# ball_dropper_rev3.net
KiCad netlist of a schematic drawn in Altium Designer
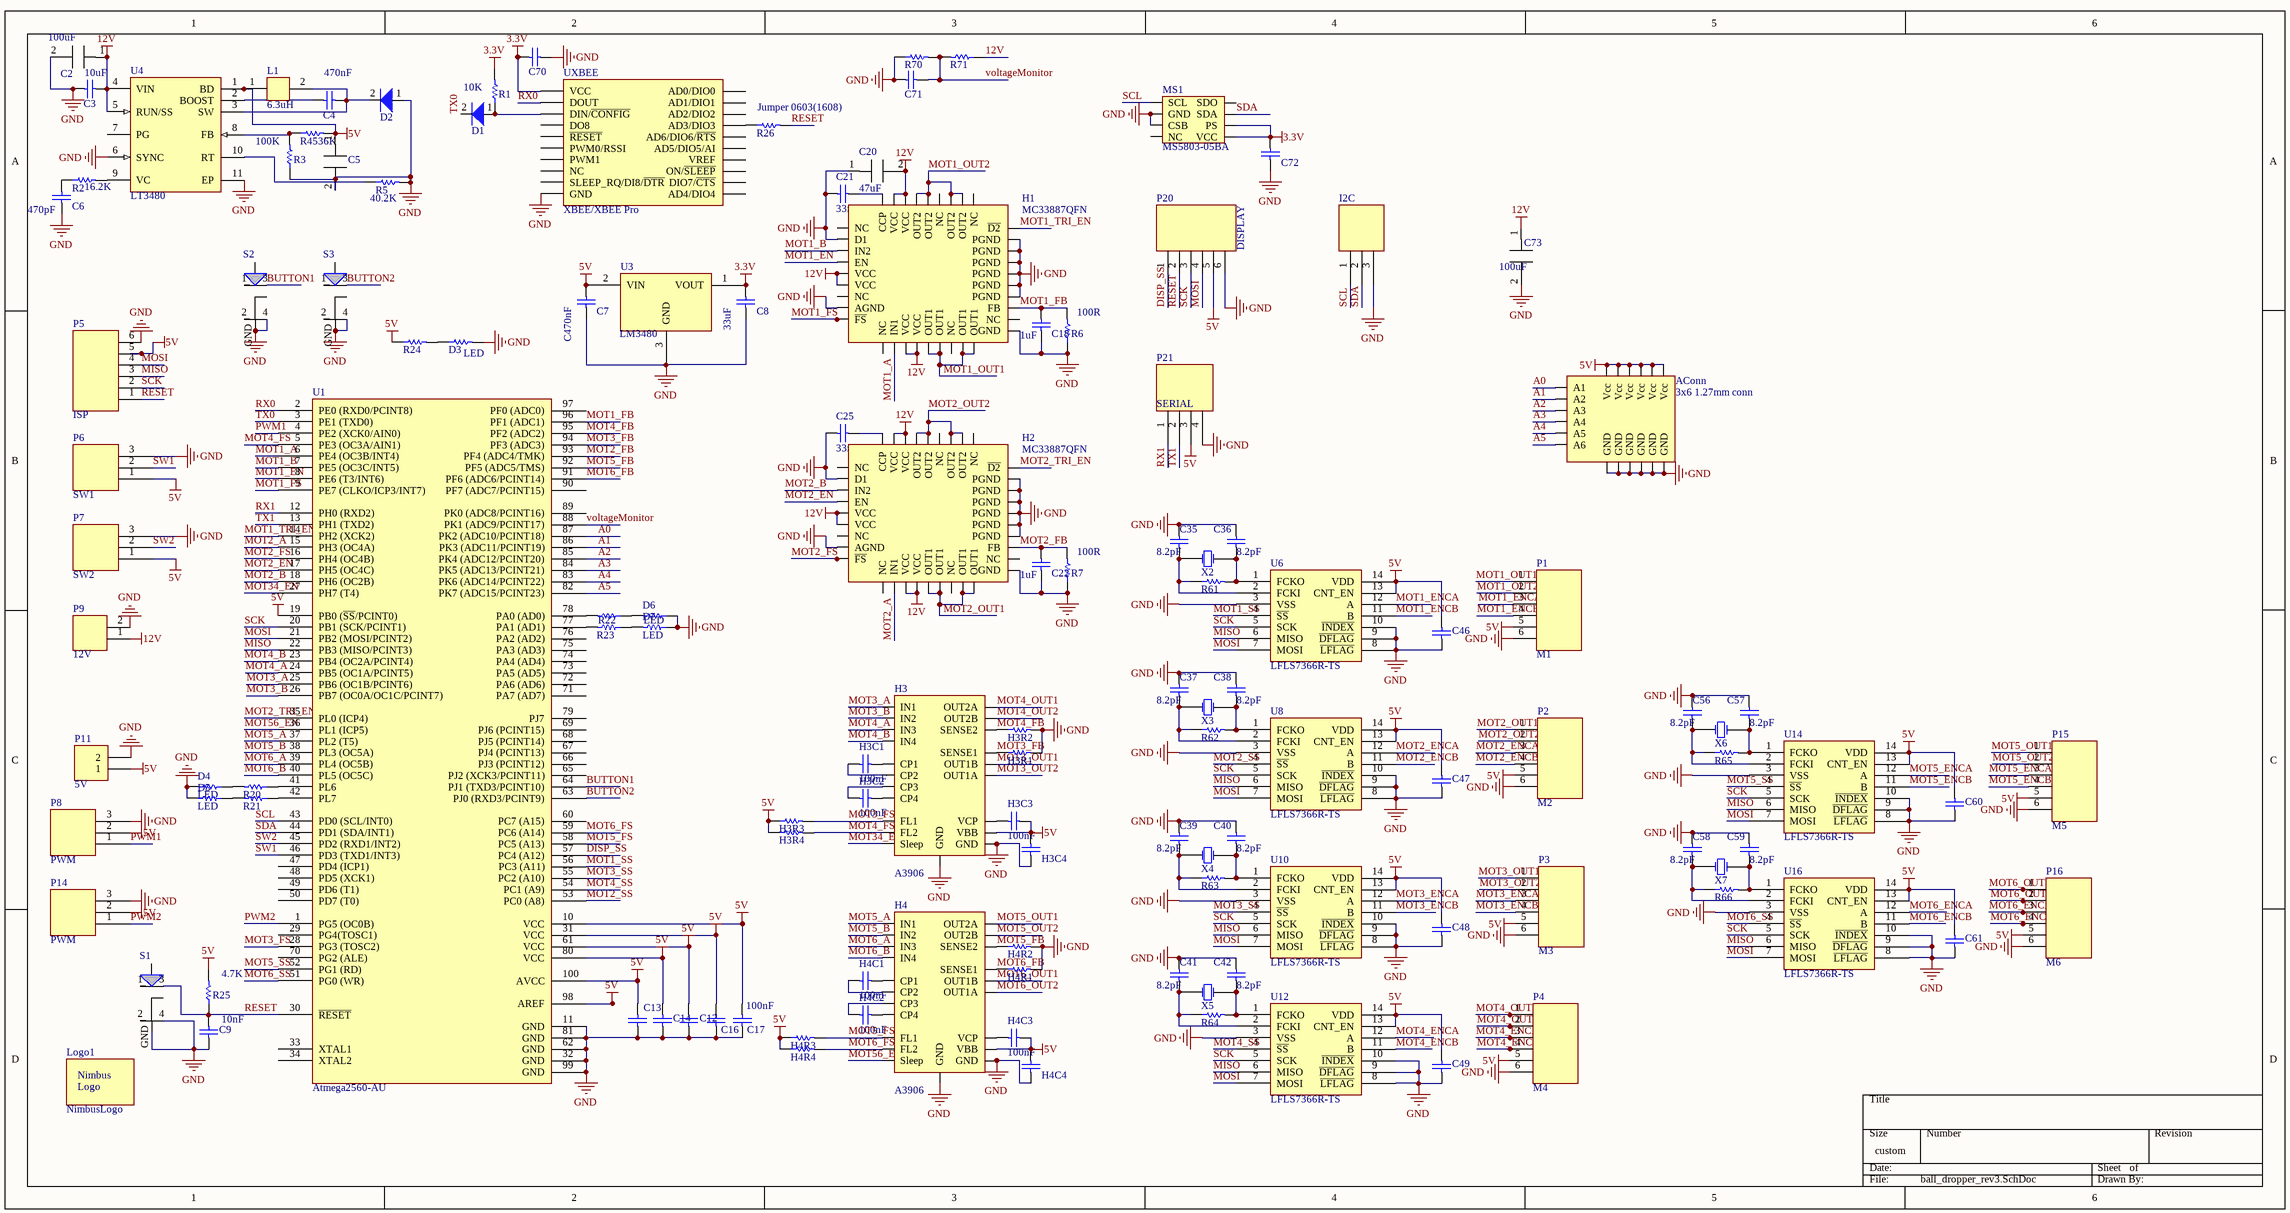
[diagram p0: ball_dropper_rev3.SchDoc]

(export (version "E")
  (design (tool "Eeschema 10.0.6"))
  (components
    (comp (ref "AConn")
      (value "3x6 1.27mm conn")
      (footprint "3x6 1.27mm conn")
      (libsource (lib "Integrated_Library") (part "3x6 1.27mm conn"))
    )
    (comp (ref "C2")
      (value "100uF")
      (footprint "TantalumCap7343")
      (libsource (lib "Integrated_Library") (part "TantalumCap7343"))
    )
    (comp (ref "C3")
      (value "10uF")
      (footprint "CAPC0603(1608)100_M")
      (description "CAP 10uF 10V ±20% 0603 (1608 Metric) Thickness 1mm SMD")
      (fields (field (name "TOLERANCE") "±20%"))
      (libsource (lib "Altium Content Vault") (part "CMP-1035-02800-1"))
    )
    (comp (ref "C4")
      (value "470nF")
      (footprint "CAPC0603(1608)100_N")
      (description "CAP 470nF 16V ±20% 0603 (1608 Metric) Thickness 1mm SMD")
      (fields (field (name "TOLERANCE") "±20%"))
      (libsource (lib "Altium Content Vault") (part "CMP-1035-02701-1"))
    )
    (comp (ref "C5")
      (value "47uF")
      (footprint "TantalumCap7343")
      (libsource (lib "Integrated_Library") (part "TantalumCap7343"))
    )
    (comp (ref "C6")
      (value "470pF")
      (footprint "CAPC0603(1608)100_N")
      (description "CAP 470pF 16V ±2% 0603 (1608 Metric) Thickness 1mm SMD")
      (fields (field (name "TOLERANCE") "±2%"))
      (libsource (lib "Altium Content Vault") (part "CMP-1035-01664-1"))
    )
    (comp (ref "C7")
      (value "C470nF")
      (footprint "CAPC0603(1608)100_N")
      (description "CAP 470nF 10V ±10% 0603 (1608 Metric) Thickness 1mm SMD")
      (fields (field (name "TOLERANCE") "±10%"))
      (libsource (lib "Altium Content Vault") (part "CMP-1035-02696-1"))
    )
    (comp (ref "C8")
      (value "33uF")
      (footprint "CAPC1206(3216)190_M")
      (description "CAP 33uF 10V ±20% 1206 (3216 Metric) Thickness 1.9mm SMD")
      (fields (field (name "TOLERANCE") "±20%"))
      (libsource (lib "Altium Content Vault") (part "CMP-1037-04997-1"))
    )
    (comp (ref "C9")
      (value "10nF")
      (footprint "CAPC0603(1608)100_M")
      (description "CAP 10nF 10V ±2% 0603 (1608 Metric) Thickness 1mm SMD")
      (fields (field (name "TOLERANCE") "±2%"))
      (libsource (lib "Altium Content Vault") (part "CMP-1035-02304-1"))
    )
    (comp (ref "C12")
      (value "100nF")
      (footprint "CAPC0603(1608)100_N")
      (description "CAP 100nF 10V -20% to +80% 0603 (1608 Metric) Thickness 1mm SMD")
      (fields (field (name "TOLERANCE") "-20% to +80%"))
      (libsource (lib "Altium Content Vault") (part "CMP-1035-02582-1"))
    )
    (comp (ref "C13")
      (value "100nF")
      (footprint "CAPC0603(1608)100_N")
      (description "CAP 100nF 10V -20% to +80% 0603 (1608 Metric) Thickness 1mm SMD")
      (fields (field (name "TOLERANCE") "-20% to +80%"))
      (libsource (lib "Altium Content Vault") (part "CMP-1035-02582-1"))
    )
    (comp (ref "C14")
      (value "100nF")
      (footprint "CAPC0603(1608)100_N")
      (description "CAP 100nF 10V -20% to +80% 0603 (1608 Metric) Thickness 1mm SMD")
      (fields (field (name "TOLERANCE") "-20% to +80%"))
      (libsource (lib "Altium Content Vault") (part "CMP-1035-02582-1"))
    )
    (comp (ref "C16")
      (value "100nF")
      (footprint "CAPC0603(1608)100_N")
      (description "CAP 100nF 10V -20% to +80% 0603 (1608 Metric) Thickness 1mm SMD")
      (fields (field (name "TOLERANCE") "-20% to +80%"))
      (libsource (lib "Altium Content Vault") (part "CMP-1035-02582-1"))
    )
    (comp (ref "C17")
      (value "100nF")
      (footprint "CAPC0603(1608)100_N")
      (description "CAP 100nF 10V -20% to +80% 0603 (1608 Metric) Thickness 1mm SMD")
      (fields (field (name "TOLERANCE") "-20% to +80%"))
      (libsource (lib "Altium Content Vault") (part "CMP-1035-02582-1"))
    )
    (comp (ref "C18")
      (value "1uF")
      (footprint "CAPC0603(1608)100_N")
      (description "CAP 1uF 25V ±10% 0603 (1608 Metric) Thickness 1mm SMD")
      (fields (field (name "TOLERANCE") "±10%"))
      (libsource (lib "Altium Content Vault") (part "CMP-1035-02740-1"))
    )
    (comp (ref "C20")
      (value "47uF")
      (footprint "TantalumCap7343")
      (libsource (lib "Integrated_Library") (part "TantalumCap7343"))
    )
    (comp (ref "C21")
      (value "33nF")
      (footprint "CAPC0603(1608)100_N")
      (description "CAP 33nF 25V ±5% 0603 (1608 Metric) Thickness 1mm SMD")
      (fields (field (name "TOLERANCE") "±5%"))
      (libsource (lib "Altium Content Vault") (part "CMP-1035-02463-1"))
    )
    (comp (ref "C22")
      (value "1uF")
      (footprint "CAPC0603(1608)100_N")
      (description "CAP 1uF 25V ±10% 0603 (1608 Metric) Thickness 1mm SMD")
      (fields (field (name "TOLERANCE") "±10%"))
      (libsource (lib "Altium Content Vault") (part "CMP-1035-02740-1"))
    )
    (comp (ref "C25")
      (value "33nF")
      (footprint "CAPC0603(1608)100_N")
      (description "CAP 33nF 25V ±5% 0603 (1608 Metric) Thickness 1mm SMD")
      (fields (field (name "TOLERANCE") "±5%"))
      (libsource (lib "Altium Content Vault") (part "CMP-1035-02463-1"))
    )
    (comp (ref "C35")
      (value "8.2pF")
      (footprint "CAPC0603(1608)100_N")
      (description "CAP 8.2pF 10V ±0.1pF 0603 (1608 Metric) Thickness 1mm SMD")
      (fields (field (name "TOLERANCE") "±0.1pF"))
      (libsource (lib "Altium Content Vault") (part "CMP-1035-00477-1"))
    )
    (comp (ref "C36")
      (value "8.2pF")
      (footprint "CAPC0603(1608)100_N")
      (description "CAP 8.2pF 10V ±0.1pF 0603 (1608 Metric) Thickness 1mm SMD")
      (fields (field (name "TOLERANCE") "±0.1pF"))
      (libsource (lib "Altium Content Vault") (part "CMP-1035-00477-1"))
    )
    (comp (ref "C37")
      (value "8.2pF")
      (footprint "CAPC0603(1608)100_N")
      (description "CAP 8.2pF 10V ±0.1pF 0603 (1608 Metric) Thickness 1mm SMD")
      (fields (field (name "TOLERANCE") "±0.1pF"))
      (libsource (lib "Altium Content Vault") (part "CMP-1035-00477-1"))
    )
    (comp (ref "C38")
      (value "8.2pF")
      (footprint "CAPC0603(1608)100_N")
      (description "CAP 8.2pF 10V ±0.1pF 0603 (1608 Metric) Thickness 1mm SMD")
      (fields (field (name "TOLERANCE") "±0.1pF"))
      (libsource (lib "Altium Content Vault") (part "CMP-1035-00477-1"))
    )
    (comp (ref "C39")
      (value "8.2pF")
      (footprint "CAPC0603(1608)100_N")
      (description "CAP 8.2pF 10V ±0.1pF 0603 (1608 Metric) Thickness 1mm SMD")
      (fields (field (name "TOLERANCE") "±0.1pF"))
      (libsource (lib "Altium Content Vault") (part "CMP-1035-00477-1"))
    )
    (comp (ref "C40")
      (value "8.2pF")
      (footprint "CAPC0603(1608)100_N")
      (description "CAP 8.2pF 10V ±0.1pF 0603 (1608 Metric) Thickness 1mm SMD")
      (fields (field (name "TOLERANCE") "±0.1pF"))
      (libsource (lib "Altium Content Vault") (part "CMP-1035-00477-1"))
    )
    (comp (ref "C41")
      (value "8.2pF")
      (footprint "CAPC0603(1608)100_N")
      (description "CAP 8.2pF 10V ±0.1pF 0603 (1608 Metric) Thickness 1mm SMD")
      (fields (field (name "TOLERANCE") "±0.1pF"))
      (libsource (lib "Altium Content Vault") (part "CMP-1035-00477-1"))
    )
    (comp (ref "C42")
      (value "8.2pF")
      (footprint "CAPC0603(1608)100_N")
      (description "CAP 8.2pF 10V ±0.1pF 0603 (1608 Metric) Thickness 1mm SMD")
      (fields (field (name "TOLERANCE") "±0.1pF"))
      (libsource (lib "Altium Content Vault") (part "CMP-1035-00477-1"))
    )
    (comp (ref "C46")
      (value "100nF")
      (footprint "CAPC0603(1608)100_N")
      (description "CAP 100nF 10V -20% to +80% 0603 (1608 Metric) Thickness 1mm SMD")
      (fields (field (name "TOLERANCE") "-20% to +80%"))
      (libsource (lib "Altium Content Vault") (part "CMP-1035-02582-1"))
    )
    (comp (ref "C47")
      (value "100nF")
      (footprint "CAPC0603(1608)100_N")
      (description "CAP 100nF 10V -20% to +80% 0603 (1608 Metric) Thickness 1mm SMD")
      (fields (field (name "TOLERANCE") "-20% to +80%"))
      (libsource (lib "Altium Content Vault") (part "CMP-1035-02582-1"))
    )
    (comp (ref "C48")
      (value "100nF")
      (footprint "CAPC0603(1608)100_N")
      (description "CAP 100nF 10V -20% to +80% 0603 (1608 Metric) Thickness 1mm SMD")
      (fields (field (name "TOLERANCE") "-20% to +80%"))
      (libsource (lib "Altium Content Vault") (part "CMP-1035-02582-1"))
    )
    (comp (ref "C49")
      (value "100nF")
      (footprint "CAPC0603(1608)100_N")
      (description "CAP 100nF 10V -20% to +80% 0603 (1608 Metric) Thickness 1mm SMD")
      (fields (field (name "TOLERANCE") "-20% to +80%"))
      (libsource (lib "Altium Content Vault") (part "CMP-1035-02582-1"))
    )
    (comp (ref "C56")
      (value "8.2pF")
      (footprint "CAPC0603(1608)100_N")
      (description "CAP 8.2pF 10V ±0.1pF 0603 (1608 Metric) Thickness 1mm SMD")
      (fields (field (name "TOLERANCE") "±0.1pF"))
      (libsource (lib "Altium Content Vault") (part "CMP-1035-00477-1"))
    )
    (comp (ref "C57")
      (value "8.2pF")
      (footprint "CAPC0603(1608)100_N")
      (description "CAP 8.2pF 10V ±0.1pF 0603 (1608 Metric) Thickness 1mm SMD")
      (fields (field (name "TOLERANCE") "±0.1pF"))
      (libsource (lib "Altium Content Vault") (part "CMP-1035-00477-1"))
    )
    (comp (ref "C58")
      (value "8.2pF")
      (footprint "CAPC0603(1608)100_N")
      (description "CAP 8.2pF 10V ±0.1pF 0603 (1608 Metric) Thickness 1mm SMD")
      (fields (field (name "TOLERANCE") "±0.1pF"))
      (libsource (lib "Altium Content Vault") (part "CMP-1035-00477-1"))
    )
    (comp (ref "C59")
      (value "8.2pF")
      (footprint "CAPC0603(1608)100_N")
      (description "CAP 8.2pF 10V ±0.1pF 0603 (1608 Metric) Thickness 1mm SMD")
      (fields (field (name "TOLERANCE") "±0.1pF"))
      (libsource (lib "Altium Content Vault") (part "CMP-1035-00477-1"))
    )
    (comp (ref "C60")
      (value "100nF")
      (footprint "CAPC0603(1608)100_N")
      (description "CAP 100nF 10V -20% to +80% 0603 (1608 Metric) Thickness 1mm SMD")
      (fields (field (name "TOLERANCE") "-20% to +80%"))
      (libsource (lib "Altium Content Vault") (part "CMP-1035-02582-1"))
    )
    (comp (ref "C61")
      (value "100nF")
      (footprint "CAPC0603(1608)100_N")
      (description "CAP 100nF 10V -20% to +80% 0603 (1608 Metric) Thickness 1mm SMD")
      (fields (field (name "TOLERANCE") "-20% to +80%"))
      (libsource (lib "Altium Content Vault") (part "CMP-1035-02582-1"))
    )
    (comp (ref "C70")
      (value "CAP 10uF 10V 1206(3216)")
      (footprint "CAPC1206(3216)190_N")
      (description "CAP 10uF 10V Â±5% 1206 (3216 Metric) Thickness 1.9mm SMD")
      (fields (field (name "TOLERANCE") "Â±5%"))
      (libsource (lib "Altium Content Vault") (part "CMP-1037-04966-1"))
    )
    (comp (ref "C71")
      (value "CAP 100nF 25V 0603(1608)")
      (footprint "CAPC0603(1608)100_N")
      (description "CAP 100nF 25V ±5% 0603 (1608 Metric) Thickness 1mm SMD")
      (fields (field (name "TOLERANCE") "Â±5%"))
      (libsource (lib "Altium Content Vault") (part "CMP-1035-02587-1"))
    )
    (comp (ref "C72")
      (value "CAP 100nF 25V 0603(1608)")
      (footprint "CAPC0603(1608)100_N")
      (description "CAP 100nF 25V ±5% 0603 (1608 Metric) Thickness 1mm SMD")
      (fields (field (name "TOLERANCE") "Â±5%"))
      (libsource (lib "Altium Content Vault") (part "CMP-1035-02587-1"))
    )
    (comp (ref "C73")
      (value "100uF")
      (footprint "TantalumCap7343")
      (libsource (lib "Integrated_Library") (part "TantalumCap7343"))
    )
    (comp (ref "D1")
      (value "diode_MBRA210LT3G")
      (footprint "C1206")
      (libsource (lib "Integrated_Library") (part "diode_MBRA210LT3G"))
    )
    (comp (ref "D2")
      (value "diode_B340A")
      (footprint "diode_B340A")
      (libsource (lib "Integrated_Library") (part "diode_B340A"))
    )
    (comp (ref "D3")
      (value "LED")
      (footprint "RESC0603(1608)_N")
      (fields (field (name "POWER") "None"))
      (libsource (lib "Altium Content Vault") (part "CMP-1012-00001-1"))
    )
    (comp (ref "D4")
      (value "LED")
      (footprint "RESC0603(1608)_N")
      (fields (field (name "POWER") "None"))
      (libsource (lib "Altium Content Vault") (part "CMP-1012-00001-1"))
    )
    (comp (ref "D5")
      (value "LED")
      (footprint "RESC0603(1608)_N")
      (fields (field (name "POWER") "None"))
      (libsource (lib "Altium Content Vault") (part "CMP-1012-00001-1"))
    )
    (comp (ref "D6")
      (value "LED")
      (footprint "RESC0603(1608)_N")
      (fields (field (name "POWER") "None"))
      (libsource (lib "Altium Content Vault") (part "CMP-1012-00001-1"))
    )
    (comp (ref "D7")
      (value "LED")
      (footprint "RESC0603(1608)_N")
      (fields (field (name "POWER") "None"))
      (libsource (lib "Altium Content Vault") (part "CMP-1012-00001-1"))
    )
    (comp (ref "H1")
      (value "MC33887QFN")
      (footprint "MC33887-QFN")
      (libsource (lib "Integrated_Library") (part "MC33887QFN"))
    )
    (comp (ref "H2")
      (value "MC33887QFN")
      (footprint "MC33887-QFN")
      (libsource (lib "Integrated_Library") (part "MC33887QFN"))
    )
    (comp (ref "H3")
      (value "A3906")
      (footprint "A3906-QFN")
      (libsource (lib "Integrated_Library") (part "A3906"))
    )
    (comp (ref "H3C1")
      (value "100nF")
      (footprint "CAPC0603(1608)100_N")
      (description "CAP 100nF 10V -20% to +80% 0603 (1608 Metric) Thickness 1mm SMD")
      (fields (field (name "TOLERANCE") "-20% to +80%"))
      (libsource (lib "Altium Content Vault") (part "CMP-1035-02582-1"))
    )
    (comp (ref "H3C2")
      (value "100nF")
      (footprint "CAPC0603(1608)100_N")
      (description "CAP 100nF 10V -20% to +80% 0603 (1608 Metric) Thickness 1mm SMD")
      (fields (field (name "TOLERANCE") "-20% to +80%"))
      (libsource (lib "Altium Content Vault") (part "CMP-1035-02582-1"))
    )
    (comp (ref "H3C3")
      (value "100nF")
      (footprint "CAPC0603(1608)100_N")
      (description "CAP 100nF 10V -20% to +80% 0603 (1608 Metric) Thickness 1mm SMD")
      (fields (field (name "TOLERANCE") "-20% to +80%"))
      (libsource (lib "Altium Content Vault") (part "CMP-1035-02582-1"))
    )
    (comp (ref "H3C4")
      (value "CAP 10uF 10V 0603(1608)")
      (footprint "CAPC0603(1608)100_N")
      (description "CAP 10uF 10V Â±10% 0603 (1608 Metric) Thickness 1mm SMD")
      (fields (field (name "TOLERANCE") "Â±10%"))
      (libsource (lib "Altium Content Vault") (part "CMP-1035-02799-1"))
    )
    (comp (ref "H3R1")
      (value "0.2R 5% 1206(3216)")
      (footprint "RESC1206(3216)_N")
      (description "0.2R 0.25W 5% 1206 (3216 Metric)  SMD")
      (fields (field (name "TOLERANCE") "5 %") (field (name "POWER") "0.25 W"))
      (libsource (lib "Altium Content Vault") (part "CMP-1014-00002-1"))
    )
    (comp (ref "H3R2")
      (value "0.2R 5% 1206(3216)")
      (footprint "RESC1206(3216)_N")
      (description "0.2R 0.25W 5% 1206 (3216 Metric)  SMD")
      (fields (field (name "TOLERANCE") "5 %") (field (name "POWER") "0.25 W"))
      (libsource (lib "Altium Content Vault") (part "CMP-1014-00002-1"))
    )
    (comp (ref "H3R3")
      (value "1M 5% 0603(1608)")
      (footprint "RESC0603(1608)_N")
      (description "1M 0.1W 5% 0603 (1608 Metric)  SMD")
      (fields (field (name "POWER") "0.1 W") (field (name "TOLERANCE") "5 %"))
      (libsource (lib "Altium Content Vault") (part "CMP-1012-00054-1"))
    )
    (comp (ref "H3R4")
      (value "1M 5% 0603(1608)")
      (footprint "RESC0603(1608)_N")
      (description "1M 0.1W 5% 0603 (1608 Metric)  SMD")
      (fields (field (name "POWER") "0.1 W") (field (name "TOLERANCE") "5 %"))
      (libsource (lib "Altium Content Vault") (part "CMP-1012-00054-1"))
    )
    (comp (ref "H4")
      (value "A3906")
      (footprint "A3906-QFN")
      (libsource (lib "Integrated_Library") (part "A3906"))
    )
    (comp (ref "H4C1")
      (value "100nF")
      (footprint "CAPC0603(1608)100_N")
      (description "CAP 100nF 10V -20% to +80% 0603 (1608 Metric) Thickness 1mm SMD")
      (fields (field (name "TOLERANCE") "-20% to +80%"))
      (libsource (lib "Altium Content Vault") (part "CMP-1035-02582-1"))
    )
    (comp (ref "H4C2")
      (value "100nF")
      (footprint "CAPC0603(1608)100_N")
      (description "CAP 100nF 10V -20% to +80% 0603 (1608 Metric) Thickness 1mm SMD")
      (fields (field (name "TOLERANCE") "-20% to +80%"))
      (libsource (lib "Altium Content Vault") (part "CMP-1035-02582-1"))
    )
    (comp (ref "H4C3")
      (value "100nF")
      (footprint "CAPC0603(1608)100_N")
      (description "CAP 100nF 10V -20% to +80% 0603 (1608 Metric) Thickness 1mm SMD")
      (fields (field (name "TOLERANCE") "-20% to +80%"))
      (libsource (lib "Altium Content Vault") (part "CMP-1035-02582-1"))
    )
    (comp (ref "H4C4")
      (value "CAP 10uF 10V 0603(1608)")
      (footprint "CAPC0603(1608)100_N")
      (description "CAP 10uF 10V Â±10% 0603 (1608 Metric) Thickness 1mm SMD")
      (fields (field (name "TOLERANCE") "Â±10%"))
      (libsource (lib "Altium Content Vault") (part "CMP-1035-02799-1"))
    )
    (comp (ref "H4R1")
      (value "0.2R 5% 1206(3216)")
      (footprint "RESC1206(3216)_N")
      (description "0.2R 0.25W 5% 1206 (3216 Metric)  SMD")
      (fields (field (name "TOLERANCE") "5 %") (field (name "POWER") "0.25 W"))
      (libsource (lib "Altium Content Vault") (part "CMP-1014-00002-1"))
    )
    (comp (ref "H4R2")
      (value "0.2R 5% 1206(3216)")
      (footprint "RESC1206(3216)_N")
      (description "0.2R 0.25W 5% 1206 (3216 Metric)  SMD")
      (fields (field (name "TOLERANCE") "5 %") (field (name "POWER") "0.25 W"))
      (libsource (lib "Altium Content Vault") (part "CMP-1014-00002-1"))
    )
    (comp (ref "H4R3")
      (value "1M 5% 0603(1608)")
      (footprint "RESC0603(1608)_N")
      (description "1M 0.1W 5% 0603 (1608 Metric)  SMD")
      (fields (field (name "POWER") "0.1 W") (field (name "TOLERANCE") "5 %"))
      (libsource (lib "Altium Content Vault") (part "CMP-1012-00054-1"))
    )
    (comp (ref "H4R4")
      (value "1M 5% 0603(1608)")
      (footprint "RESC0603(1608)_N")
      (description "1M 0.1W 5% 0603 (1608 Metric)  SMD")
      (fields (field (name "POWER") "0.1 W") (field (name "TOLERANCE") "5 %"))
      (libsource (lib "Altium Content Vault") (part "CMP-1012-00054-1"))
    )
    (comp (ref "I2C") (value "Hirose3") (footprint "DF3A-3P-2DS-RA") (libsource (lib "") (part "Hirose3_1")))
    (comp (ref "L1")
      (value "6.3uH")
      (footprint "CDRH62B")
      (libsource (lib "Integrated_Library") (part "TYS6045_inductor"))
    )
    (comp (ref "Logo1")
      (value "NimbusLogo")
      (footprint "NIMBUS Logo")
      (libsource (lib "Integrated_Library") (part "NimbusLogo"))
    )
    (comp (ref "MS1")
      (value "MS5803-05BA")
      (footprint "MS5803-05BA")
      (libsource (lib "Integrated_Library") (part "MS5803-05BA"))
    )
    (comp (ref "P1")
      (value "M1")
      (footprint "DF3A-6P-2DS")
      (libsource (lib "Integrated_Library") (part "Hirose6"))
    )
    (comp (ref "P2")
      (value "M2")
      (footprint "DF3A-6P-2DS")
      (libsource (lib "Integrated_Library") (part "Hirose6"))
    )
    (comp (ref "P3")
      (value "M3")
      (footprint "DF3A-6P-2DS")
      (libsource (lib "Integrated_Library") (part "Hirose6"))
    )
    (comp (ref "P4")
      (value "M4")
      (footprint "DF3A-6P-2DS")
      (libsource (lib "Integrated_Library") (part "Hirose6"))
    )
    (comp (ref "P5") (value "ISP") (footprint "DF3A-6P-2DS") (libsource (lib "") (part "Hirose6_2")))
    (comp (ref "P6")
      (value "SW1")
      (footprint "DF3A-3P-2DS-RA")
      (libsource (lib "Integrated_Library") (part "Hirose3"))
    )
    (comp (ref "P7")
      (value "SW2")
      (footprint "DF3A-3P-2DS-RA")
      (libsource (lib "Integrated_Library") (part "Hirose3"))
    )
    (comp (ref "P8")
      (value "PWM")
      (footprint "DF3A-3P-2DS")
      (libsource (lib "Integrated_Library") (part "Hirose3"))
    )
    (comp (ref "P9")
      (value "12V")
      (footprint "DF3A-2P-2DS Vert")
      (libsource (lib "Integrated_Library") (part "Hirose2"))
    )
    (comp (ref "P11")
      (value "5V")
      (footprint "DF3A-2P-2DS")
      (description "Header, 2-Pin")
      (fields (field (name "PUBLISHER") "Altium Limited"))
      (libsource (lib "Miscellaneous Connectors") (part "Header 2"))
    )
    (comp (ref "P14")
      (value "PWM")
      (footprint "DF3A-3P-2DS")
      (libsource (lib "Integrated_Library") (part "Hirose3"))
    )
    (comp (ref "P15")
      (value "M5")
      (footprint "DF3A-6P-2DS")
      (libsource (lib "Integrated_Library") (part "Hirose6"))
    )
    (comp (ref "P16")
      (value "M6")
      (footprint "DF3A-6P-2DS")
      (libsource (lib "Integrated_Library") (part "Hirose6"))
    )
    (comp (ref "P20") (value "DISPLAY") (footprint "DF3A-6P-2DS") (libsource (lib "") (part "Hirose6_1")))
    (comp (ref "P21")
      (value "SERIAL")
      (footprint "DF3A-4P-2DS")
      (libsource (lib "Integrated_Library") (part "Hirose4"))
    )
    (comp (ref "R1")
      (value "10K")
      (footprint "RESC0603(1608)_N")
      (description "10K 0.1W 5% 0603 (1608 Metric)  SMD")
      (fields (field (name "TOLERANCE") "5 %") (field (name "POWER") "0.1 W"))
      (libsource (lib "Altium Content Vault") (part "CMP-1012-00098-1"))
    )
    (comp (ref "R2")
      (value "16.2K")
      (footprint "RESC0603(1608)_N")
      (description "16K2 0.1W 1% 0603 (1608 Metric)  SMD")
      (fields (field (name "POWER") "0.1 W") (field (name "TOLERANCE") "1 %"))
      (libsource (lib "Altium Content Vault") (part "CMP-1012-00645-1"))
    )
    (comp (ref "R3")
      (value "100K")
      (footprint "RESC0603(1608)_N")
      (description "100K 0.1W 5% 0603 (1608 Metric)  SMD")
      (fields (field (name "TOLERANCE") "5 %") (field (name "POWER") "0.1 W"))
      (libsource (lib "Altium Content Vault") (part "CMP-1012-00122-1"))
    )
    (comp (ref "R4")
      (value "536K")
      (footprint "RESC0603(1608)_M")
      (description "536K 0.1W 1% 0603 (1608 Metric)  SMD")
      (fields (field (name "TOLERANCE") "1 %") (field (name "POWER") "0.1 W"))
      (libsource (lib "Altium Content Vault") (part "CMP-1012-00819-1"))
    )
    (comp (ref "R5")
      (value "40.2K")
      (footprint "RESC0603(1608)_M")
      (description "40K2 0.1W 1% 0603 (1608 Metric)  SMD")
      (fields (field (name "TOLERANCE") "1 %") (field (name "POWER") "0.1 W"))
      (libsource (lib "Altium Content Vault") (part "CMP-1012-00691-1"))
    )
    (comp (ref "R6")
      (value "100R")
      (footprint "RESC0603(1608)_N")
      (description "100R 0.1W 5% 0603 (1608 Metric)  SMD")
      (fields (field (name "TOLERANCE") "5 %") (field (name "POWER") "0.1 W"))
      (libsource (lib "Altium Content Vault") (part "CMP-1012-00050-1"))
    )
    (comp (ref "R7")
      (value "100R")
      (footprint "RESC0603(1608)_N")
      (description "100R 0.1W 5% 0603 (1608 Metric)  SMD")
      (fields (field (name "TOLERANCE") "5 %") (field (name "POWER") "0.1 W"))
      (libsource (lib "Altium Content Vault") (part "CMP-1012-00050-1"))
    )
    (comp (ref "R20")
      (value "150R 5% 0603(1608)")
      (footprint "RESC0603(1608)_N")
      (description "150R 0.1W 5% 0603 (1608 Metric)  SMD")
      (fields (field (name "POWER") "0.1 W") (field (name "TOLERANCE") "5 %"))
      (libsource (lib "Altium Content Vault") (part "CMP-1012-00054-1"))
    )
    (comp (ref "R21")
      (value "150R 5% 0603(1608)")
      (footprint "RESC0603(1608)_N")
      (description "150R 0.1W 5% 0603 (1608 Metric)  SMD")
      (fields (field (name "POWER") "0.1 W") (field (name "TOLERANCE") "5 %"))
      (libsource (lib "Altium Content Vault") (part "CMP-1012-00054-1"))
    )
    (comp (ref "R22")
      (value "150R 5% 0603(1608)")
      (footprint "RESC0603(1608)_N")
      (description "150R 0.1W 5% 0603 (1608 Metric)  SMD")
      (fields (field (name "POWER") "0.1 W") (field (name "TOLERANCE") "5 %"))
      (libsource (lib "Altium Content Vault") (part "CMP-1012-00054-1"))
    )
    (comp (ref "R23")
      (value "150R 5% 0603(1608)")
      (footprint "RESC0603(1608)_N")
      (description "150R 0.1W 5% 0603 (1608 Metric)  SMD")
      (fields (field (name "POWER") "0.1 W") (field (name "TOLERANCE") "5 %"))
      (libsource (lib "Altium Content Vault") (part "CMP-1012-00054-1"))
    )
    (comp (ref "R24")
      (value "150R 5% 0603(1608)")
      (footprint "RESC0603(1608)_N")
      (description "150R 0.1W 5% 0603 (1608 Metric)  SMD")
      (fields (field (name "POWER") "0.1 W") (field (name "TOLERANCE") "5 %"))
      (libsource (lib "Altium Content Vault") (part "CMP-1012-00054-1"))
    )
    (comp (ref "R25")
      (value "4.7K")
      (footprint "RESC0603(1608)_N")
      (description "4K7 0.1W 5% 0603 (1608 Metric)  SMD")
      (fields (field (name "TOLERANCE") "5 %") (field (name "POWER") "0.1 W"))
      (libsource (lib "Altium Content Vault") (part "CMP-1012-00090-1"))
    )
    (comp (ref "R26")
      (value "Jumper 0603(1608)")
      (footprint "RESC0603(1608)_N")
      (description "Jumper 0603 (1608 Metric)")
      (fields (field (name "POWER") "None"))
      (libsource (lib "Altium Content Vault") (part "CMP-1012-00001-1"))
    )
    (comp (ref "R61")
      (value "1M 5% 0603(1608)")
      (footprint "RESC0603(1608)_N")
      (description "1M 0.1W 5% 0603 (1608 Metric)  SMD")
      (fields (field (name "POWER") "0.1 W") (field (name "TOLERANCE") "5 %"))
      (libsource (lib "Altium Content Vault") (part "CMP-1012-00146-1"))
    )
    (comp (ref "R62")
      (value "1M 5% 0603(1608)")
      (footprint "RESC0603(1608)_N")
      (description "1M 0.1W 5% 0603 (1608 Metric)  SMD")
      (fields (field (name "POWER") "0.1 W") (field (name "TOLERANCE") "5 %"))
      (libsource (lib "Altium Content Vault") (part "CMP-1012-00146-1"))
    )
    (comp (ref "R63")
      (value "1M 5% 0603(1608)")
      (footprint "RESC0603(1608)_N")
      (description "1M 0.1W 5% 0603 (1608 Metric)  SMD")
      (fields (field (name "POWER") "0.1 W") (field (name "TOLERANCE") "5 %"))
      (libsource (lib "Altium Content Vault") (part "CMP-1012-00146-1"))
    )
    (comp (ref "R64")
      (value "1M 5% 0603(1608)")
      (footprint "RESC0603(1608)_N")
      (description "1M 0.1W 5% 0603 (1608 Metric)  SMD")
      (fields (field (name "POWER") "0.1 W") (field (name "TOLERANCE") "5 %"))
      (libsource (lib "Altium Content Vault") (part "CMP-1012-00146-1"))
    )
    (comp (ref "R65")
      (value "1M 5% 0603(1608)")
      (footprint "RESC0603(1608)_N")
      (description "1M 0.1W 5% 0603 (1608 Metric)  SMD")
      (fields (field (name "POWER") "0.1 W") (field (name "TOLERANCE") "5 %"))
      (libsource (lib "Altium Content Vault") (part "CMP-1012-00146-1"))
    )
    (comp (ref "R66")
      (value "1M 5% 0603(1608)")
      (footprint "RESC0603(1608)_N")
      (description "1M 0.1W 5% 0603 (1608 Metric)  SMD")
      (fields (field (name "POWER") "0.1 W") (field (name "TOLERANCE") "5 %"))
      (libsource (lib "Altium Content Vault") (part "CMP-1012-00146-1"))
    )
    (comp (ref "R70")
      (value "27K 1% 0603(1608)")
      (footprint "RESC0603(1608)_N")
      (description "27K 0.1W 1% 0603 (1608 Metric)  SMD")
      (fields (field (name "POWER") "0.1 W") (field (name "TOLERANCE") "1 %"))
      (libsource (lib "Altium Content Vault") (part "CMP-1012-00670-1"))
    )
    (comp (ref "R71")
      (value "90K9 1% 0603(1608)")
      (footprint "RESC0603(1608)_N")
      (description "90K9 0.1W 1% 0603 (1608 Metric)  SMD")
      (fields (field (name "POWER") "0.1 W") (field (name "TOLERANCE") "1 %"))
      (libsource (lib "Altium Content Vault") (part "CMP-1012-00731-1"))
    )
    (comp (ref "S1")
      (value "TactileSwitch_lp")
      (footprint "LOW_PROFILE_W_GND")
      (libsource (lib "Integrated_Library") (part "TactileSwitch_lp"))
    )
    (comp (ref "S2")
      (value "TactileSwitch_lp")
      (footprint "LOW_PROFILE_W_GND")
      (libsource (lib "Integrated_Library") (part "TactileSwitch_lp"))
    )
    (comp (ref "S3")
      (value "TactileSwitch_lp")
      (footprint "LOW_PROFILE_W_GND")
      (libsource (lib "Integrated_Library") (part "TactileSwitch_lp"))
    )
    (comp (ref "U1")
      (value "Atmega2560-AU")
      (footprint "TSQFP50P1600X1600X160-100N")
      (description "ATMEGA2560-16AURCT-ND")
      (libsource (lib "Integrated_Library") (part "Atmega2560-AU"))
    )
    (comp (ref "U3")
      (value "LM3480")
      (footprint "LM3480")
      (description "LM3480IM3-3.3/NOPBCT-ND")
      (libsource (lib "Integrated_Library") (part "LM3480"))
    )
    (comp (ref "U4")
      (value "LT3480")
      (footprint "LT-MSE-10-EDP_L")
      (fields
        (field (name "PARTNUMBER") "LT3480EMSE#TRPBF")
        (field (name "MANUFACTURER") "Linear Technology")
      )
      (libsource (lib "Altium Content Vault") (part "CMP-0491-01005-1"))
    )
    (comp (ref "U6")
      (value "LFLS7366R-TS")
      (footprint "LS7366RTS")
      (libsource (lib "Integrated_Library") (part "LFLS7366R-TS"))
    )
    (comp (ref "U8")
      (value "LFLS7366R-TS")
      (footprint "LS7366RTS")
      (libsource (lib "Integrated_Library") (part "LFLS7366R-TS"))
    )
    (comp (ref "U10")
      (value "LFLS7366R-TS")
      (footprint "LS7366RTS")
      (libsource (lib "Integrated_Library") (part "LFLS7366R-TS"))
    )
    (comp (ref "U12")
      (value "LFLS7366R-TS")
      (footprint "LS7366RTS")
      (libsource (lib "Integrated_Library") (part "LFLS7366R-TS"))
    )
    (comp (ref "U14")
      (value "LFLS7366R-TS")
      (footprint "LS7366RTS")
      (libsource (lib "Integrated_Library") (part "LFLS7366R-TS"))
    )
    (comp (ref "U16")
      (value "LFLS7366R-TS")
      (footprint "LS7366RTS")
      (libsource (lib "Integrated_Library") (part "LFLS7366R-TS"))
    )
    (comp (ref "UXBEE")
      (value "XBEE/XBEE Pro")
      (footprint "XBEE - Surface Mount")
      (libsource (lib "Integrated_Library") (part "Xbee Pro"))
    )
    (comp (ref "X2")
      (value "40MHz")
      (footprint "xtal4")
      (libsource (lib "Integrated_Library") (part "xtal4"))
    )
    (comp (ref "X3")
      (value "40MHz")
      (footprint "xtal4")
      (libsource (lib "Integrated_Library") (part "xtal4"))
    )
    (comp (ref "X4")
      (value "40MHz")
      (footprint "xtal4")
      (libsource (lib "Integrated_Library") (part "xtal4"))
    )
    (comp (ref "X5")
      (value "40MHz")
      (footprint "xtal4")
      (libsource (lib "Integrated_Library") (part "xtal4"))
    )
    (comp (ref "X6")
      (value "40MHz")
      (footprint "xtal4")
      (libsource (lib "Integrated_Library") (part "xtal4"))
    )
    (comp (ref "X7")
      (value "40MHz")
      (footprint "xtal4")
      (libsource (lib "Integrated_Library") (part "xtal4"))
    )
  )
  (nets
    (net (code "1") (name "/A0") (class "Default")
      (node (ref "AConn") (pin "3") (pinfunction "A1_3") (pintype "passive"))
      (node (ref "U1") (pin "87") (pinfunction "PK2_(ADC10/PCINT18)_87") (pintype "passive"))
    )
    (net (code "2") (name "/A1") (class "Default")
      (node (ref "AConn") (pin "6") (pinfunction "A2_6") (pintype "passive"))
      (node (ref "U1") (pin "86") (pinfunction "PK3_(ADC11/PCINT19)_86") (pintype "passive"))
    )
    (net (code "3") (name "/A2") (class "Default")
      (node (ref "AConn") (pin "9") (pinfunction "A3_9") (pintype "passive"))
      (node (ref "U1") (pin "85") (pinfunction "PK4_(ADC12/PCINT20)_85") (pintype "passive"))
    )
    (net (code "4") (name "/A3") (class "Default")
      (node (ref "AConn") (pin "12") (pinfunction "A4_12") (pintype "passive"))
      (node (ref "U1") (pin "84") (pinfunction "PK5_(ADC13/PCINT21)_84") (pintype "passive"))
    )
    (net (code "5") (name "/A4") (class "Default")
      (node (ref "AConn") (pin "15") (pinfunction "A5_15") (pintype "passive"))
      (node (ref "U1") (pin "83") (pinfunction "PK6_(ADC14/PCINT22)_83") (pintype "passive"))
    )
    (net (code "6") (name "/A5") (class "Default")
      (node (ref "AConn") (pin "18") (pinfunction "A6_18") (pintype "passive"))
      (node (ref "U1") (pin "82") (pinfunction "PK7_(ADC15/PCINT23)_82") (pintype "passive"))
    )
    (net (code "7") (name "/BUTTON1") (class "Default")
      (node (ref "S2") (pin "3") (pinfunction "GND_3") (pintype "passive"))
      (node (ref "U1") (pin "64") (pinfunction "PJ1_(TXD3/PCINT10)_64") (pintype "passive"))
    )
    (net (code "8") (name "/BUTTON2") (class "Default")
      (node (ref "S3") (pin "3") (pinfunction "GND_3") (pintype "passive"))
      (node (ref "U1") (pin "63") (pinfunction "PJ0_(RXD3/PCINT9)_63") (pintype "passive"))
    )
    (net (code "9") (name "/DISP_SS") (class "Default")
      (node (ref "P20") (pin "1") (pintype "passive"))
      (node (ref "U1") (pin "57") (pinfunction "PC4_(A12)_57") (pintype "passive"))
    )
    (net (code "10") (name "/MISO") (class "Default")
      (node (ref "P5") (pin "3") (pintype "passive"))
      (node (ref "U1") (pin "22") (pinfunction "PB3_(MISO/PCINT3)_22") (pintype "passive"))
      (node (ref "U10") (pin "6") (pinfunction "MISO_6") (pintype "passive"))
      (node (ref "U12") (pin "6") (pinfunction "MISO_6") (pintype "passive"))
      (node (ref "U14") (pin "6") (pinfunction "MISO_6") (pintype "passive"))
      (node (ref "U16") (pin "6") (pinfunction "MISO_6") (pintype "passive"))
      (node (ref "U6") (pin "6") (pinfunction "MISO_6") (pintype "passive"))
      (node (ref "U8") (pin "6") (pinfunction "MISO_6") (pintype "passive"))
    )
    (net (code "11") (name "/MOSI") (class "Default")
      (node (ref "P20") (pin "4") (pintype "passive"))
      (node (ref "P5") (pin "4") (pintype "passive"))
      (node (ref "U1") (pin "21") (pinfunction "PB2_(MOSI/PCINT2)_21") (pintype "passive"))
      (node (ref "U10") (pin "7") (pinfunction "MOSI_7") (pintype "passive"))
      (node (ref "U12") (pin "7") (pinfunction "MOSI_7") (pintype "passive"))
      (node (ref "U14") (pin "7") (pinfunction "MOSI_7") (pintype "passive"))
      (node (ref "U16") (pin "7") (pinfunction "MOSI_7") (pintype "passive"))
      (node (ref "U6") (pin "7") (pinfunction "MOSI_7") (pintype "passive"))
      (node (ref "U8") (pin "7") (pinfunction "MOSI_7") (pintype "passive"))
    )
    (net (code "12") (name "/MOT1_A") (class "Default")
      (node (ref "H1") (pin "11") (pinfunction "IN1_11") (pintype "passive"))
      (node (ref "U1") (pin "6") (pinfunction "PE4_(OC3B/INT4)_6") (pintype "passive"))
    )
    (net (code "13") (name "/MOT1_B") (class "Default")
      (node (ref "H1") (pin "3") (pinfunction "IN2_3") (pintype "passive"))
      (node (ref "U1") (pin "7") (pinfunction "PE5_(OC3C/INT5)_7") (pintype "passive"))
    )
    (net (code "14") (name "/MOT1_EN") (class "Default")
      (node (ref "H1") (pin "4") (pinfunction "EN_4") (pintype "passive"))
      (node (ref "U1") (pin "8") (pinfunction "PE6_(T3/INT6)_8") (pintype "passive"))
    )
    (net (code "15") (name "/MOT1_ENCA") (class "Default")
      (node (ref "P1") (pin "3") (pintype "passive"))
      (node (ref "U6") (pin "12") (pinfunction "A_12") (pintype "passive"))
    )
    (net (code "16") (name "/MOT1_ENCB") (class "Default")
      (node (ref "P1") (pin "4") (pintype "passive"))
      (node (ref "U6") (pin "11") (pinfunction "B_11") (pintype "passive"))
    )
    (net (code "17") (name "/MOT1_FB") (class "Default")
      (node (ref "C18") (pin "2") (pinfunction "2_2") (pintype "passive"))
      (node (ref "H1") (pin "20") (pinfunction "FB_20") (pintype "passive"))
      (node (ref "R6") (pin "2") (pinfunction "2_2") (pintype "passive"))
      (node (ref "U1") (pin "96") (pinfunction "PF1_(ADC1)_96") (pintype "passive"))
    )
    (net (code "18") (name "/MOT1_FS") (class "Default")
      (node (ref "H1") (pin "9") (pinfunction "~{FS}_9") (pintype "passive"))
      (node (ref "U1") (pin "9") (pinfunction "PE7_(CLKO/ICP3/INT7)_9") (pintype "passive"))
    )
    (net (code "19") (name "/MOT1_OUT1") (class "Default")
      (node (ref "H1") (pin "14") (pinfunction "OUT1_14") (pintype "passive"))
      (node (ref "H1") (pin "15") (pinfunction "OUT1_15") (pintype "passive"))
      (node (ref "H1") (pin "17") (pinfunction "OUT1_17") (pintype "passive"))
      (node (ref "H1") (pin "18") (pinfunction "OUT1_18") (pintype "passive"))
      (node (ref "P1") (pin "1") (pintype "passive"))
    )
    (net (code "20") (name "/MOT1_OUT2") (class "Default")
      (node (ref "H1") (pin "29") (pinfunction "OUT2_29") (pintype "passive"))
      (node (ref "H1") (pin "30") (pinfunction "OUT2_30") (pintype "passive"))
      (node (ref "H1") (pin "32") (pinfunction "OUT2_32") (pintype "passive"))
      (node (ref "H1") (pin "33") (pinfunction "OUT2_33") (pintype "passive"))
      (node (ref "P1") (pin "2") (pintype "passive"))
    )
    (net (code "21") (name "/MOT1_SS") (class "Default")
      (node (ref "U1") (pin "56") (pinfunction "PC3_(A11)_56") (pintype "passive"))
      (node (ref "U6") (pin "4") (pinfunction "~{SS}_4") (pintype "passive"))
    )
    (net (code "22") (name "/MOT1_TRI_EN") (class "Default")
      (node (ref "H1") (pin "27") (pinfunction "~{D2}_27") (pintype "passive"))
      (node (ref "U1") (pin "14") (pinfunction "PH2_(XCK2)_14") (pintype "passive"))
    )
    (net (code "23") (name "/MOT2_A") (class "Default")
      (node (ref "H2") (pin "11") (pinfunction "IN1_11") (pintype "passive"))
      (node (ref "U1") (pin "15") (pinfunction "PH3_(OC4A)_15") (pintype "passive"))
    )
    (net (code "24") (name "/MOT2_B") (class "Default")
      (node (ref "H2") (pin "3") (pinfunction "IN2_3") (pintype "passive"))
      (node (ref "U1") (pin "18") (pinfunction "PH6_(OC2B)_18") (pintype "passive"))
    )
    (net (code "25") (name "/MOT2_EN") (class "Default")
      (node (ref "H2") (pin "4") (pinfunction "EN_4") (pintype "passive"))
      (node (ref "U1") (pin "17") (pinfunction "PH5_(OC4C)_17") (pintype "passive"))
    )
    (net (code "26") (name "/MOT2_ENCA") (class "Default")
      (node (ref "P2") (pin "3") (pintype "passive"))
      (node (ref "U8") (pin "12") (pinfunction "A_12") (pintype "passive"))
    )
    (net (code "27") (name "/MOT2_ENCB") (class "Default")
      (node (ref "P2") (pin "4") (pintype "passive"))
      (node (ref "U8") (pin "11") (pinfunction "B_11") (pintype "passive"))
    )
    (net (code "28") (name "/MOT2_FB") (class "Default")
      (node (ref "C22") (pin "2") (pinfunction "2_2") (pintype "passive"))
      (node (ref "H2") (pin "20") (pinfunction "FB_20") (pintype "passive"))
      (node (ref "R7") (pin "2") (pinfunction "2_2") (pintype "passive"))
      (node (ref "U1") (pin "93") (pinfunction "PF4_(ADC4/TMK)_93") (pintype "passive"))
    )
    (net (code "29") (name "/MOT2_FS") (class "Default")
      (node (ref "H2") (pin "9") (pinfunction "~{FS}_9") (pintype "passive"))
      (node (ref "U1") (pin "16") (pinfunction "PH4_(OC4B)_16") (pintype "passive"))
    )
    (net (code "30") (name "/MOT2_OUT1") (class "Default")
      (node (ref "H2") (pin "14") (pinfunction "OUT1_14") (pintype "passive"))
      (node (ref "H2") (pin "15") (pinfunction "OUT1_15") (pintype "passive"))
      (node (ref "H2") (pin "17") (pinfunction "OUT1_17") (pintype "passive"))
      (node (ref "H2") (pin "18") (pinfunction "OUT1_18") (pintype "passive"))
      (node (ref "P2") (pin "1") (pintype "passive"))
    )
    (net (code "31") (name "/MOT2_OUT2") (class "Default")
      (node (ref "H2") (pin "29") (pinfunction "OUT2_29") (pintype "passive"))
      (node (ref "H2") (pin "30") (pinfunction "OUT2_30") (pintype "passive"))
      (node (ref "H2") (pin "32") (pinfunction "OUT2_32") (pintype "passive"))
      (node (ref "H2") (pin "33") (pinfunction "OUT2_33") (pintype "passive"))
      (node (ref "P2") (pin "2") (pintype "passive"))
    )
    (net (code "32") (name "/MOT2_SS") (class "Default")
      (node (ref "U1") (pin "53") (pinfunction "PC0_(A8)_53") (pintype "passive"))
      (node (ref "U8") (pin "4") (pinfunction "~{SS}_4") (pintype "passive"))
    )
    (net (code "33") (name "/MOT2_TRI_EN") (class "Default")
      (node (ref "H2") (pin "27") (pinfunction "~{D2}_27") (pintype "passive"))
      (node (ref "U1") (pin "35") (pinfunction "PL0_(ICP4)_35") (pintype "passive"))
    )
    (net (code "34") (name "/MOT3_A") (class "Default")
      (node (ref "H3") (pin "4") (pinfunction "IN1_4") (pintype "passive"))
      (node (ref "U1") (pin "25") (pinfunction "PB6_(OC1B/PCINT6)_25") (pintype "passive"))
    )
    (net (code "35") (name "/MOT3_B") (class "Default")
      (node (ref "H3") (pin "5") (pinfunction "IN2_5") (pintype "passive"))
      (node (ref "U1") (pin "26") (pinfunction "PB7_(OC0A/OC1C/PCINT7)_26") (pintype "passive"))
    )
    (net (code "36") (name "/MOT3_ENCA") (class "Default")
      (node (ref "P3") (pin "3") (pintype "passive"))
      (node (ref "U10") (pin "12") (pinfunction "A_12") (pintype "passive"))
    )
    (net (code "37") (name "/MOT3_ENCB") (class "Default")
      (node (ref "P3") (pin "4") (pintype "passive"))
      (node (ref "U10") (pin "11") (pinfunction "B_11") (pintype "passive"))
    )
    (net (code "38") (name "/MOT3_FB") (class "Default")
      (node (ref "H3") (pin "15") (pinfunction "SENSE1_15") (pintype "passive"))
      (node (ref "H3R1") (pin "1") (pinfunction "1_1") (pintype "passive"))
      (node (ref "U1") (pin "94") (pinfunction "PF3_(ADC3)_94") (pintype "passive"))
    )
    (net (code "39") (name "/MOT3_FS") (class "Default")
      (node (ref "H3") (pin "8") (pinfunction "FL1_8") (pintype "passive"))
      (node (ref "H3R3") (pin "2") (pinfunction "2_2") (pintype "passive"))
      (node (ref "U1") (pin "28") (pinfunction "PG3_(TOSC2)_28") (pintype "passive"))
    )
    (net (code "40") (name "/MOT3_OUT1") (class "Default")
      (node (ref "H3") (pin "14") (pinfunction "OUT1B_14") (pintype "passive"))
      (node (ref "P3") (pin "1") (pintype "passive"))
    )
    (net (code "41") (name "/MOT3_OUT2") (class "Default")
      (node (ref "H3") (pin "16") (pinfunction "OUT1A_16") (pintype "passive"))
      (node (ref "P3") (pin "2") (pintype "passive"))
    )
    (net (code "42") (name "/MOT3_SS") (class "Default")
      (node (ref "U1") (pin "55") (pinfunction "PC2_(A10)_55") (pintype "passive"))
      (node (ref "U10") (pin "4") (pinfunction "~{SS}_4") (pintype "passive"))
    )
    (net (code "43") (name "/MOT4_A") (class "Default")
      (node (ref "H3") (pin "6") (pinfunction "IN3_6") (pintype "passive"))
      (node (ref "U1") (pin "24") (pinfunction "PB5_(OC1A/PCINT5)_24") (pintype "passive"))
    )
    (net (code "44") (name "/MOT4_B") (class "Default")
      (node (ref "H3") (pin "7") (pinfunction "IN4_7") (pintype "passive"))
      (node (ref "U1") (pin "23") (pinfunction "PB4_(OC2A/PCINT4)_23") (pintype "passive"))
    )
    (net (code "45") (name "/MOT4_ENCA") (class "Default")
      (node (ref "P4") (pin "3") (pintype "passive"))
      (node (ref "U12") (pin "12") (pinfunction "A_12") (pintype "passive"))
    )
    (net (code "46") (name "/MOT4_ENCB") (class "Default")
      (node (ref "P4") (pin "4") (pintype "passive"))
      (node (ref "U12") (pin "11") (pinfunction "B_11") (pintype "passive"))
    )
    (net (code "47") (name "/MOT4_FB") (class "Default")
      (node (ref "H3") (pin "11") (pinfunction "SENSE2_11") (pintype "passive"))
      (node (ref "H3R2") (pin "1") (pinfunction "1_1") (pintype "passive"))
      (node (ref "U1") (pin "95") (pinfunction "PF2_(ADC2)_95") (pintype "passive"))
    )
    (net (code "48") (name "/MOT4_FS") (class "Default")
      (node (ref "H3") (pin "9") (pinfunction "FL2_9") (pintype "passive"))
      (node (ref "H3R4") (pin "2") (pinfunction "2_2") (pintype "passive"))
      (node (ref "U1") (pin "5") (pinfunction "PE3_(OC3A/AIN1)_5") (pintype "passive"))
    )
    (net (code "49") (name "/MOT4_OUT1") (class "Default")
      (node (ref "H3") (pin "10") (pinfunction "OUT2A_10") (pintype "passive"))
      (node (ref "P4") (pin "1") (pintype "passive"))
    )
    (net (code "50") (name "/MOT4_OUT2") (class "Default")
      (node (ref "H3") (pin "12") (pinfunction "OUT2B_12") (pintype "passive"))
      (node (ref "P4") (pin "2") (pintype "passive"))
    )
    (net (code "51") (name "/MOT4_SS") (class "Default")
      (node (ref "U1") (pin "54") (pinfunction "PC1_(A9)_54") (pintype "passive"))
      (node (ref "U12") (pin "4") (pinfunction "~{SS}_4") (pintype "passive"))
    )
    (net (code "52") (name "/MOT5_A") (class "Default")
      (node (ref "H4") (pin "4") (pinfunction "IN1_4") (pintype "passive"))
      (node (ref "U1") (pin "37") (pinfunction "PL2_(T5)_37") (pintype "passive"))
    )
    (net (code "53") (name "/MOT5_B") (class "Default")
      (node (ref "H4") (pin "5") (pinfunction "IN2_5") (pintype "passive"))
      (node (ref "U1") (pin "38") (pinfunction "PL3_(OC5A)_38") (pintype "passive"))
    )
    (net (code "54") (name "/MOT5_ENCA") (class "Default")
      (node (ref "P15") (pin "3") (pintype "passive"))
      (node (ref "U14") (pin "12") (pinfunction "A_12") (pintype "passive"))
    )
    (net (code "55") (name "/MOT5_ENCB") (class "Default")
      (node (ref "P15") (pin "4") (pintype "passive"))
      (node (ref "U14") (pin "11") (pinfunction "B_11") (pintype "passive"))
    )
    (net (code "56") (name "/MOT5_FB") (class "Default")
      (node (ref "H4") (pin "11") (pinfunction "SENSE2_11") (pintype "passive"))
      (node (ref "H4R2") (pin "1") (pinfunction "1_1") (pintype "passive"))
      (node (ref "U1") (pin "92") (pinfunction "PF5_(ADC5/TMS)_92") (pintype "passive"))
    )
    (net (code "57") (name "/MOT5_FS") (class "Default")
      (node (ref "H4") (pin "8") (pinfunction "FL1_8") (pintype "passive"))
      (node (ref "H4R3") (pin "2") (pinfunction "2_2") (pintype "passive"))
      (node (ref "U1") (pin "58") (pinfunction "PC5_(A13)_58") (pintype "passive"))
    )
    (net (code "58") (name "/MOT5_OUT1") (class "Default")
      (node (ref "H4") (pin "10") (pinfunction "OUT2A_10") (pintype "passive"))
      (node (ref "P15") (pin "1") (pintype "passive"))
    )
    (net (code "59") (name "/MOT5_OUT2") (class "Default")
      (node (ref "H4") (pin "12") (pinfunction "OUT2B_12") (pintype "passive"))
      (node (ref "P15") (pin "2") (pintype "passive"))
    )
    (net (code "60") (name "/MOT5_SS") (class "Default")
      (node (ref "U1") (pin "52") (pinfunction "PG1_(RD)_52") (pintype "passive"))
      (node (ref "U14") (pin "4") (pinfunction "~{SS}_4") (pintype "passive"))
    )
    (net (code "61") (name "/MOT6_A") (class "Default")
      (node (ref "H4") (pin "6") (pinfunction "IN3_6") (pintype "passive"))
      (node (ref "U1") (pin "39") (pinfunction "PL4_(OC5B)_39") (pintype "passive"))
    )
    (net (code "62") (name "/MOT6_B") (class "Default")
      (node (ref "H4") (pin "7") (pinfunction "IN4_7") (pintype "passive"))
      (node (ref "U1") (pin "40") (pinfunction "PL5_(OC5C)_40") (pintype "passive"))
    )
    (net (code "63") (name "/MOT6_ENCA") (class "Default")
      (node (ref "P16") (pin "3") (pintype "passive"))
      (node (ref "U16") (pin "12") (pinfunction "A_12") (pintype "passive"))
    )
    (net (code "64") (name "/MOT6_ENCB") (class "Default")
      (node (ref "P16") (pin "4") (pintype "passive"))
      (node (ref "U16") (pin "11") (pinfunction "B_11") (pintype "passive"))
    )
    (net (code "65") (name "/MOT6_FB") (class "Default")
      (node (ref "H4") (pin "15") (pinfunction "SENSE1_15") (pintype "passive"))
      (node (ref "H4R1") (pin "1") (pinfunction "1_1") (pintype "passive"))
      (node (ref "U1") (pin "91") (pinfunction "PF6_(ADC6/PCINT14)_91") (pintype "passive"))
    )
    (net (code "66") (name "/MOT6_FS") (class "Default")
      (node (ref "H4") (pin "9") (pinfunction "FL2_9") (pintype "passive"))
      (node (ref "H4R4") (pin "2") (pinfunction "2_2") (pintype "passive"))
      (node (ref "U1") (pin "59") (pinfunction "PC6_(A14)_59") (pintype "passive"))
    )
    (net (code "67") (name "/MOT6_OUT1") (class "Default")
      (node (ref "H4") (pin "14") (pinfunction "OUT1B_14") (pintype "passive"))
      (node (ref "P16") (pin "1") (pintype "passive"))
    )
    (net (code "68") (name "/MOT6_OUT2") (class "Default")
      (node (ref "H4") (pin "16") (pinfunction "OUT1A_16") (pintype "passive"))
      (node (ref "P16") (pin "2") (pintype "passive"))
    )
    (net (code "69") (name "/MOT6_SS") (class "Default")
      (node (ref "U1") (pin "51") (pinfunction "PG0_(WR)_51") (pintype "passive"))
      (node (ref "U16") (pin "4") (pinfunction "~{SS}_4") (pintype "passive"))
    )
    (net (code "70") (name "/MOT34_EN") (class "Default")
      (node (ref "H3") (pin "3") (pinfunction "Sleep_3") (pintype "passive"))
      (node (ref "U1") (pin "27") (pinfunction "PH7_(T4)_27") (pintype "passive"))
    )
    (net (code "71") (name "/MOT56_EN") (class "Default")
      (node (ref "H4") (pin "3") (pinfunction "Sleep_3") (pintype "passive"))
      (node (ref "U1") (pin "36") (pinfunction "PL1_(ICP5)_36") (pintype "passive"))
    )
    (net (code "72") (name "/PWM1") (class "Default")
      (node (ref "P8") (pin "1") (pinfunction "7_1") (pintype "passive"))
      (node (ref "U1") (pin "4") (pinfunction "PE2_(XCK0/AIN0)_4") (pintype "passive"))
    )
    (net (code "73") (name "/PWM2") (class "Default")
      (node (ref "P14") (pin "1") (pinfunction "7_1") (pintype "passive"))
      (node (ref "U1") (pin "1") (pinfunction "PG5_(OC0B)_1") (pintype "passive"))
    )
    (net (code "74") (name "/RESET") (class "Default")
      (node (ref "C9") (pin "2") (pinfunction "2_2") (pintype "passive"))
      (node (ref "P20") (pin "2") (pintype "passive"))
      (node (ref "P5") (pin "1") (pintype "passive"))
      (node (ref "R25") (pin "1") (pinfunction "1_1") (pintype "passive"))
      (node (ref "R26") (pin "2") (pinfunction "2_2") (pintype "passive"))
      (node (ref "S1") (pin "3") (pinfunction "GND_3") (pintype "passive"))
      (node (ref "U1") (pin "30") (pinfunction "~{RESET}_30") (pintype "passive"))
    )
    (net (code "75") (name "/RX0") (class "Default")
      (node (ref "U1") (pin "2") (pinfunction "PE0_(RXD0/PCINT8)_2") (pintype "passive"))
      (node (ref "UXBEE") (pin "2") (pinfunction "DOUT_2") (pintype "passive"))
    )
    (net (code "76") (name "/RX1") (class "Default")
      (node (ref "P21") (pin "1") (pinfunction "7_1") (pintype "passive"))
      (node (ref "U1") (pin "12") (pinfunction "PH0_(RXD2)_12") (pintype "passive"))
    )
    (net (code "77") (name "/SCK") (class "Default")
      (node (ref "P20") (pin "3") (pintype "passive"))
      (node (ref "P5") (pin "2") (pintype "passive"))
      (node (ref "U1") (pin "20") (pinfunction "PB1_(SCK/PCINT1)_20") (pintype "passive"))
      (node (ref "U10") (pin "5") (pinfunction "SCK_5") (pintype "passive"))
      (node (ref "U12") (pin "5") (pinfunction "SCK_5") (pintype "passive"))
      (node (ref "U14") (pin "5") (pinfunction "SCK_5") (pintype "passive"))
      (node (ref "U16") (pin "5") (pinfunction "SCK_5") (pintype "passive"))
      (node (ref "U6") (pin "5") (pinfunction "SCK_5") (pintype "passive"))
      (node (ref "U8") (pin "5") (pinfunction "SCK_5") (pintype "passive"))
    )
    (net (code "78") (name "/SCL") (class "Default")
      (node (ref "I2C") (pin "1") (pinfunction "7_1") (pintype "passive"))
      (node (ref "MS1") (pin "1") (pinfunction "SCL_1") (pintype "passive"))
      (node (ref "U1") (pin "43") (pinfunction "PD0_(SCL/INT0)_43") (pintype "passive"))
    )
    (net (code "79") (name "/SDA") (class "Default")
      (node (ref "I2C") (pin "2") (pinfunction "8_2") (pintype "passive"))
      (node (ref "MS1") (pin "7") (pinfunction "SDA_7") (pintype "passive"))
      (node (ref "U1") (pin "44") (pinfunction "PD1_(SDA/INT1)_44") (pintype "passive"))
    )
    (net (code "80") (name "/SW1") (class "Default")
      (node (ref "P6") (pin "2") (pinfunction "8_2") (pintype "passive"))
      (node (ref "U1") (pin "46") (pinfunction "PD3_(TXD1/INT3)_46") (pintype "passive"))
    )
    (net (code "81") (name "/SW2") (class "Default")
      (node (ref "P7") (pin "2") (pinfunction "8_2") (pintype "passive"))
      (node (ref "U1") (pin "45") (pinfunction "PD2_(RXD1/INT2)_45") (pintype "passive"))
    )
    (net (code "82") (name "/TX0") (class "Default")
      (node (ref "D1") (pin "2") (pinfunction "6_2") (pintype "passive"))
      (node (ref "U1") (pin "3") (pinfunction "PE1_(TXD0)_3") (pintype "passive"))
    )
    (net (code "83") (name "/TX1") (class "Default")
      (node (ref "P21") (pin "2") (pinfunction "8_2") (pintype "passive"))
      (node (ref "U1") (pin "13") (pinfunction "PH1_(TXD2)_13") (pintype "passive"))
    )
    (net (code "84") (name "/voltageMonitor") (class "Default")
      (node (ref "C71") (pin "2") (pinfunction "2_2") (pintype "passive"))
      (node (ref "R70") (pin "2") (pinfunction "2_2") (pintype "passive"))
      (node (ref "R71") (pin "2") (pinfunction "2_2") (pintype "passive"))
      (node (ref "U1") (pin "88") (pinfunction "PK1_(ADC9/PCINT17)_88") (pintype "passive"))
    )
    (net (code "85") (name "3.3V") (class "Default")
      (node (ref "C70") (pin "1") (pinfunction "1_1") (pintype "passive"))
      (node (ref "C72") (pin "2") (pinfunction "2_2") (pintype "passive"))
      (node (ref "C8") (pin "2") (pinfunction "2_2") (pintype "passive"))
      (node (ref "MS1") (pin "5") (pinfunction "VCC_5") (pintype "passive"))
      (node (ref "MS1") (pin "6") (pinfunction "PS_6") (pintype "passive"))
      (node (ref "R1") (pin "2") (pinfunction "2_2") (pintype "passive"))
      (node (ref "U3") (pin "1") (pinfunction "VOUT_1") (pintype "passive"))
      (node (ref "UXBEE") (pin "1") (pinfunction "VCC_1") (pintype "passive"))
    )
    (net (code "86") (name "5V") (class "Default")
      (node (ref "AConn") (pin "11") (pinfunction "Vcc_11") (pintype "passive"))
      (node (ref "AConn") (pin "14") (pinfunction "Vcc_14") (pintype "passive"))
      (node (ref "AConn") (pin "17") (pinfunction "Vcc_17") (pintype "passive"))
      (node (ref "AConn") (pin "2") (pinfunction "Vcc_2") (pintype "passive"))
      (node (ref "AConn") (pin "5") (pinfunction "Vcc_5") (pintype "passive"))
      (node (ref "AConn") (pin "8") (pinfunction "Vcc_8") (pintype "passive"))
      (node (ref "C12") (pin "2") (pinfunction "2_2") (pintype "passive"))
      (node (ref "C13") (pin "2") (pinfunction "2_2") (pintype "passive"))
      (node (ref "C14") (pin "2") (pinfunction "2_2") (pintype "passive"))
      (node (ref "C16") (pin "2") (pinfunction "2_2") (pintype "passive"))
      (node (ref "C17") (pin "2") (pinfunction "2_2") (pintype "passive"))
      (node (ref "C46") (pin "2") (pinfunction "2_2") (pintype "passive"))
      (node (ref "C47") (pin "2") (pinfunction "2_2") (pintype "passive"))
      (node (ref "C48") (pin "2") (pinfunction "2_2") (pintype "passive"))
      (node (ref "C49") (pin "2") (pinfunction "2_2") (pintype "passive"))
      (node (ref "C5") (pin "1") (pinfunction "VCC_1") (pintype "passive"))
      (node (ref "C60") (pin "2") (pinfunction "2_2") (pintype "passive"))
      (node (ref "C61") (pin "2") (pinfunction "2_2") (pintype "passive"))
      (node (ref "C7") (pin "2") (pinfunction "2_2") (pintype "passive"))
      (node (ref "H3") (pin "13") (pinfunction "VBB_13") (pintype "passive"))
      (node (ref "H3C3") (pin "1") (pinfunction "1_1") (pintype "passive"))
      (node (ref "H3C4") (pin "2") (pinfunction "2_2") (pintype "passive"))
      (node (ref "H3R3") (pin "1") (pinfunction "1_1") (pintype "passive"))
      (node (ref "H3R4") (pin "1") (pinfunction "1_1") (pintype "passive"))
      (node (ref "H4") (pin "13") (pinfunction "VBB_13") (pintype "passive"))
      (node (ref "H4C3") (pin "1") (pinfunction "1_1") (pintype "passive"))
      (node (ref "H4C4") (pin "2") (pinfunction "2_2") (pintype "passive"))
      (node (ref "H4R3") (pin "1") (pinfunction "1_1") (pintype "passive"))
      (node (ref "H4R4") (pin "1") (pinfunction "1_1") (pintype "passive"))
      (node (ref "L1") (pin "1") (pintype "passive"))
      (node (ref "P1") (pin "5") (pintype "passive"))
      (node (ref "P11") (pin "1") (pinfunction "1_1") (pintype "passive"))
      (node (ref "P14") (pin "2") (pinfunction "8_2") (pintype "passive"))
      (node (ref "P15") (pin "5") (pintype "passive"))
      (node (ref "P16") (pin "5") (pintype "passive"))
      (node (ref "P2") (pin "5") (pintype "passive"))
      (node (ref "P20") (pin "5") (pintype "passive"))
      (node (ref "P21") (pin "3") (pinfunction "9_3") (pintype "passive"))
      (node (ref "P3") (pin "5") (pintype "passive"))
      (node (ref "P4") (pin "5") (pintype "passive"))
      (node (ref "P5") (pin "5") (pintype "passive"))
      (node (ref "P6") (pin "1") (pinfunction "7_1") (pintype "passive"))
      (node (ref "P7") (pin "1") (pinfunction "7_1") (pintype "passive"))
      (node (ref "P8") (pin "2") (pinfunction "8_2") (pintype "passive"))
      (node (ref "R24") (pin "1") (pinfunction "1_1") (pintype "passive"))
      (node (ref "R25") (pin "2") (pinfunction "2_2") (pintype "passive"))
      (node (ref "R4") (pin "2") (pinfunction "2_2") (pintype "passive"))
      (node (ref "U1") (pin "10") (pinfunction "VCC_10") (pintype "passive"))
      (node (ref "U1") (pin "100") (pinfunction "AVCC_100") (pintype "passive"))
      (node (ref "U1") (pin "19") (pinfunction "PB0_(~{SS}/PCINT0)_19") (pintype "passive"))
      (node (ref "U1") (pin "31") (pinfunction "VCC_31") (pintype "passive"))
      (node (ref "U1") (pin "61") (pinfunction "VCC_61") (pintype "passive"))
      (node (ref "U1") (pin "80") (pinfunction "VCC_80") (pintype "passive"))
      (node (ref "U1") (pin "98") (pinfunction "AREF_98") (pintype "passive"))
      (node (ref "U10") (pin "13") (pinfunction "CNT_EN_13") (pintype "passive"))
      (node (ref "U10") (pin "14") (pinfunction "VDD_14") (pintype "passive"))
      (node (ref "U12") (pin "13") (pinfunction "CNT_EN_13") (pintype "passive"))
      (node (ref "U12") (pin "14") (pinfunction "VDD_14") (pintype "passive"))
      (node (ref "U14") (pin "13") (pinfunction "CNT_EN_13") (pintype "passive"))
      (node (ref "U14") (pin "14") (pinfunction "VDD_14") (pintype "passive"))
      (node (ref "U16") (pin "13") (pinfunction "CNT_EN_13") (pintype "passive"))
      (node (ref "U16") (pin "14") (pinfunction "VDD_14") (pintype "passive"))
      (node (ref "U3") (pin "2") (pinfunction "VIN_2") (pintype "passive"))
      (node (ref "U4") (pin "1") (pinfunction "BD_1") (pintype "power_in"))
      (node (ref "U6") (pin "13") (pinfunction "CNT_EN_13") (pintype "passive"))
      (node (ref "U6") (pin "14") (pinfunction "VDD_14") (pintype "passive"))
      (node (ref "U8") (pin "13") (pinfunction "CNT_EN_13") (pintype "passive"))
      (node (ref "U8") (pin "14") (pinfunction "VDD_14") (pintype "passive"))
    )
    (net (code "87") (name "12V") (class "Default")
      (node (ref "C2") (pin "1") (pinfunction "VCC_1") (pintype "passive"))
      (node (ref "C20") (pin "2") (pinfunction "GND_2") (pintype "passive"))
      (node (ref "C3") (pin "2") (pinfunction "2_2") (pintype "passive"))
      (node (ref "C73") (pin "1") (pinfunction "VCC_1") (pintype "passive"))
      (node (ref "H1") (pin "12") (pinfunction "VCC_12") (pintype "passive"))
      (node (ref "H1") (pin "13") (pinfunction "VCC_13") (pintype "passive"))
      (node (ref "H1") (pin "34") (pinfunction "VCC_34") (pintype "passive"))
      (node (ref "H1") (pin "35") (pinfunction "VCC_35") (pintype "passive"))
      (node (ref "H1") (pin "5") (pinfunction "VCC_5") (pintype "passive"))
      (node (ref "H1") (pin "6") (pinfunction "VCC_6") (pintype "passive"))
      (node (ref "H2") (pin "12") (pinfunction "VCC_12") (pintype "passive"))
      (node (ref "H2") (pin "13") (pinfunction "VCC_13") (pintype "passive"))
      (node (ref "H2") (pin "34") (pinfunction "VCC_34") (pintype "passive"))
      (node (ref "H2") (pin "35") (pinfunction "VCC_35") (pintype "passive"))
      (node (ref "H2") (pin "5") (pinfunction "VCC_5") (pintype "passive"))
      (node (ref "H2") (pin "6") (pinfunction "VCC_6") (pintype "passive"))
      (node (ref "P9") (pin "1") (pintype "passive"))
      (node (ref "R71") (pin "1") (pinfunction "1_1") (pintype "passive"))
      (node (ref "U4") (pin "4") (pinfunction "VIN_4") (pintype "power_in"))
      (node (ref "U4") (pin "5") (pinfunction "RUN/SS_5") (pintype "input"))
    )
    (net (code "88") (name "GND") (class "Default")
      (node (ref "AConn") (pin "1") (pinfunction "GND_1") (pintype "passive"))
      (node (ref "AConn") (pin "10") (pinfunction "GND_10") (pintype "passive"))
      (node (ref "AConn") (pin "13") (pinfunction "GND_13") (pintype "passive"))
      (node (ref "AConn") (pin "16") (pinfunction "GND_16") (pintype "passive"))
      (node (ref "AConn") (pin "4") (pinfunction "GND_4") (pintype "passive"))
      (node (ref "AConn") (pin "7") (pinfunction "GND_7") (pintype "passive"))
      (node (ref "C12") (pin "1") (pinfunction "1_1") (pintype "passive"))
      (node (ref "C13") (pin "1") (pinfunction "1_1") (pintype "passive"))
      (node (ref "C14") (pin "1") (pinfunction "1_1") (pintype "passive"))
      (node (ref "C16") (pin "1") (pinfunction "1_1") (pintype "passive"))
      (node (ref "C17") (pin "1") (pinfunction "1_1") (pintype "passive"))
      (node (ref "C18") (pin "1") (pinfunction "1_1") (pintype "passive"))
      (node (ref "C2") (pin "2") (pinfunction "GND_2") (pintype "passive"))
      (node (ref "C20") (pin "1") (pinfunction "VCC_1") (pintype "passive"))
      (node (ref "C21") (pin "1") (pinfunction "1_1") (pintype "passive"))
      (node (ref "C22") (pin "1") (pinfunction "1_1") (pintype "passive"))
      (node (ref "C25") (pin "1") (pinfunction "1_1") (pintype "passive"))
      (node (ref "C3") (pin "1") (pinfunction "1_1") (pintype "passive"))
      (node (ref "C35") (pin "2") (pinfunction "2_2") (pintype "passive"))
      (node (ref "C36") (pin "2") (pinfunction "2_2") (pintype "passive"))
      (node (ref "C37") (pin "2") (pinfunction "2_2") (pintype "passive"))
      (node (ref "C38") (pin "2") (pinfunction "2_2") (pintype "passive"))
      (node (ref "C39") (pin "2") (pinfunction "2_2") (pintype "passive"))
      (node (ref "C40") (pin "2") (pinfunction "2_2") (pintype "passive"))
      (node (ref "C41") (pin "2") (pinfunction "2_2") (pintype "passive"))
      (node (ref "C42") (pin "2") (pinfunction "2_2") (pintype "passive"))
      (node (ref "C46") (pin "1") (pinfunction "1_1") (pintype "passive"))
      (node (ref "C47") (pin "1") (pinfunction "1_1") (pintype "passive"))
      (node (ref "C48") (pin "1") (pinfunction "1_1") (pintype "passive"))
      (node (ref "C49") (pin "1") (pinfunction "1_1") (pintype "passive"))
      (node (ref "C5") (pin "2") (pinfunction "GND_2") (pintype "passive"))
      (node (ref "C56") (pin "2") (pinfunction "2_2") (pintype "passive"))
      (node (ref "C57") (pin "2") (pinfunction "2_2") (pintype "passive"))
      (node (ref "C58") (pin "2") (pinfunction "2_2") (pintype "passive"))
      (node (ref "C59") (pin "2") (pinfunction "2_2") (pintype "passive"))
      (node (ref "C6") (pin "1") (pinfunction "1_1") (pintype "passive"))
      (node (ref "C60") (pin "1") (pinfunction "1_1") (pintype "passive"))
      (node (ref "C61") (pin "1") (pinfunction "1_1") (pintype "passive"))
      (node (ref "C7") (pin "1") (pinfunction "1_1") (pintype "passive"))
      (node (ref "C70") (pin "2") (pinfunction "2_2") (pintype "passive"))
      (node (ref "C71") (pin "1") (pinfunction "1_1") (pintype "passive"))
      (node (ref "C72") (pin "1") (pinfunction "1_1") (pintype "passive"))
      (node (ref "C73") (pin "2") (pinfunction "GND_2") (pintype "passive"))
      (node (ref "C8") (pin "1") (pinfunction "1_1") (pintype "passive"))
      (node (ref "C9") (pin "1") (pinfunction "1_1") (pintype "passive"))
      (node (ref "D2") (pin "1") (pinfunction "5_1") (pintype "passive"))
      (node (ref "D3") (pin "2") (pinfunction "2_2") (pintype "passive"))
      (node (ref "D4") (pin "2") (pinfunction "2_2") (pintype "passive"))
      (node (ref "D5") (pin "2") (pinfunction "2_2") (pintype "passive"))
      (node (ref "D6") (pin "1") (pinfunction "1_1") (pintype "passive"))
      (node (ref "D7") (pin "1") (pinfunction "1_1") (pintype "passive"))
      (node (ref "H1") (pin "2") (pinfunction "D1_2") (pintype "passive"))
      (node (ref "H1") (pin "21") (pinfunction "PGND_21") (pintype "passive"))
      (node (ref "H1") (pin "22") (pinfunction "PGND_22") (pintype "passive"))
      (node (ref "H1") (pin "23") (pinfunction "PGND_23") (pintype "passive"))
      (node (ref "H1") (pin "24") (pinfunction "PGND_24") (pintype "passive"))
      (node (ref "H1") (pin "25") (pinfunction "PGND_25") (pintype "passive"))
      (node (ref "H1") (pin "26") (pinfunction "PGND_26") (pintype "passive"))
      (node (ref "H1") (pin "37") (pinfunction "GND_37") (pintype "passive"))
      (node (ref "H1") (pin "8") (pinfunction "AGND_8") (pintype "passive"))
      (node (ref "H2") (pin "2") (pinfunction "D1_2") (pintype "passive"))
      (node (ref "H2") (pin "21") (pinfunction "PGND_21") (pintype "passive"))
      (node (ref "H2") (pin "22") (pinfunction "PGND_22") (pintype "passive"))
      (node (ref "H2") (pin "23") (pinfunction "PGND_23") (pintype "passive"))
      (node (ref "H2") (pin "24") (pinfunction "PGND_24") (pintype "passive"))
      (node (ref "H2") (pin "25") (pinfunction "PGND_25") (pintype "passive"))
      (node (ref "H2") (pin "26") (pinfunction "PGND_26") (pintype "passive"))
      (node (ref "H2") (pin "37") (pinfunction "GND_37") (pintype "passive"))
      (node (ref "H2") (pin "8") (pinfunction "AGND_8") (pintype "passive"))
      (node (ref "H3") (pin "2") (pinfunction "GND_2") (pintype "passive"))
      (node (ref "H3") (pin "21") (pinfunction "GND_21") (pintype "passive"))
      (node (ref "H3C4") (pin "1") (pinfunction "1_1") (pintype "passive"))
      (node (ref "H3R1") (pin "2") (pinfunction "2_2") (pintype "passive"))
      (node (ref "H3R2") (pin "2") (pinfunction "2_2") (pintype "passive"))
      (node (ref "H4") (pin "2") (pinfunction "GND_2") (pintype "passive"))
      (node (ref "H4") (pin "21") (pinfunction "GND_21") (pintype "passive"))
      (node (ref "H4C4") (pin "1") (pinfunction "1_1") (pintype "passive"))
      (node (ref "H4R1") (pin "2") (pinfunction "2_2") (pintype "passive"))
      (node (ref "H4R2") (pin "2") (pinfunction "2_2") (pintype "passive"))
      (node (ref "I2C") (pin "3") (pinfunction "9_3") (pintype "passive"))
      (node (ref "MS1") (pin "2") (pinfunction "GND_2") (pintype "passive"))
      (node (ref "MS1") (pin "3") (pinfunction "CSB_3") (pintype "passive"))
      (node (ref "P1") (pin "6") (pintype "passive"))
      (node (ref "P11") (pin "2") (pinfunction "2_2") (pintype "passive"))
      (node (ref "P14") (pin "3") (pinfunction "9_3") (pintype "passive"))
      (node (ref "P15") (pin "6") (pintype "passive"))
      (node (ref "P16") (pin "6") (pintype "passive"))
      (node (ref "P2") (pin "6") (pintype "passive"))
      (node (ref "P20") (pin "6") (pintype "passive"))
      (node (ref "P21") (pin "4") (pinfunction "4_4") (pintype "passive"))
      (node (ref "P3") (pin "6") (pintype "passive"))
      (node (ref "P4") (pin "6") (pintype "passive"))
      (node (ref "P5") (pin "6") (pintype "passive"))
      (node (ref "P6") (pin "3") (pinfunction "9_3") (pintype "passive"))
      (node (ref "P7") (pin "3") (pinfunction "9_3") (pintype "passive"))
      (node (ref "P8") (pin "3") (pinfunction "9_3") (pintype "passive"))
      (node (ref "P9") (pin "2") (pintype "passive"))
      (node (ref "R3") (pin "1") (pinfunction "1_1") (pintype "passive"))
      (node (ref "R5") (pin "2") (pinfunction "2_2") (pintype "passive"))
      (node (ref "R6") (pin "1") (pinfunction "1_1") (pintype "passive"))
      (node (ref "R7") (pin "1") (pinfunction "1_1") (pintype "passive"))
      (node (ref "R70") (pin "1") (pinfunction "1_1") (pintype "passive"))
      (node (ref "S1") (pin "4") (pinfunction "GND_4") (pintype "passive"))
      (node (ref "S1") (pin "GND") (pinfunction "GND_GND") (pintype "passive"))
      (node (ref "S2") (pin "4") (pinfunction "GND_4") (pintype "passive"))
      (node (ref "S2") (pin "GND") (pinfunction "GND_GND") (pintype "passive"))
      (node (ref "S3") (pin "4") (pinfunction "GND_4") (pintype "passive"))
      (node (ref "S3") (pin "GND") (pinfunction "GND_GND") (pintype "passive"))
      (node (ref "U1") (pin "11") (pinfunction "GND_11") (pintype "passive"))
      (node (ref "U1") (pin "32") (pinfunction "GND_32") (pintype "passive"))
      (node (ref "U1") (pin "62") (pinfunction "GND_62") (pintype "passive"))
      (node (ref "U1") (pin "81") (pinfunction "GND_81") (pintype "passive"))
      (node (ref "U1") (pin "99") (pinfunction "GND_99") (pintype "passive"))
      (node (ref "U10") (pin "10") (pinfunction "~{INDEX}_10") (pintype "passive"))
      (node (ref "U10") (pin "3") (pinfunction "VSS_3") (pintype "passive"))
      (node (ref "U10") (pin "8") (pinfunction "~{LFLAG}_8") (pintype "passive"))
      (node (ref "U10") (pin "9") (pinfunction "~{DFLAG}_9") (pintype "passive"))
      (node (ref "U12") (pin "10") (pinfunction "~{INDEX}_10") (pintype "passive"))
      (node (ref "U12") (pin "3") (pinfunction "VSS_3") (pintype "passive"))
      (node (ref "U12") (pin "8") (pinfunction "~{LFLAG}_8") (pintype "passive"))
      (node (ref "U12") (pin "9") (pinfunction "~{DFLAG}_9") (pintype "passive"))
      (node (ref "U14") (pin "10") (pinfunction "~{INDEX}_10") (pintype "passive"))
      (node (ref "U14") (pin "3") (pinfunction "VSS_3") (pintype "passive"))
      (node (ref "U14") (pin "8") (pinfunction "~{LFLAG}_8") (pintype "passive"))
      (node (ref "U14") (pin "9") (pinfunction "~{DFLAG}_9") (pintype "passive"))
      (node (ref "U16") (pin "10") (pinfunction "~{INDEX}_10") (pintype "passive"))
      (node (ref "U16") (pin "3") (pinfunction "VSS_3") (pintype "passive"))
      (node (ref "U16") (pin "8") (pinfunction "~{LFLAG}_8") (pintype "passive"))
      (node (ref "U16") (pin "9") (pinfunction "~{DFLAG}_9") (pintype "passive"))
      (node (ref "U3") (pin "3") (pinfunction "GND_3") (pintype "passive"))
      (node (ref "U4") (pin "11") (pinfunction "EP_11") (pintype "power_in"))
      (node (ref "U4") (pin "6") (pinfunction "SYNC_6") (pintype "input"))
      (node (ref "U6") (pin "10") (pinfunction "~{INDEX}_10") (pintype "passive"))
      (node (ref "U6") (pin "3") (pinfunction "VSS_3") (pintype "passive"))
      (node (ref "U6") (pin "8") (pinfunction "~{LFLAG}_8") (pintype "passive"))
      (node (ref "U6") (pin "9") (pinfunction "~{DFLAG}_9") (pintype "passive"))
      (node (ref "U8") (pin "10") (pinfunction "~{INDEX}_10") (pintype "passive"))
      (node (ref "U8") (pin "3") (pinfunction "VSS_3") (pintype "passive"))
      (node (ref "U8") (pin "8") (pinfunction "~{LFLAG}_8") (pintype "passive"))
      (node (ref "U8") (pin "9") (pinfunction "~{DFLAG}_9") (pintype "passive"))
      (node (ref "UXBEE") (pin "10") (pinfunction "GND_10") (pintype "passive"))
    )
    (net (code "89") (name "Net-(C6-Pad2)") (class "Default")
      (node (ref "C6") (pin "2") (pinfunction "2_2") (pintype "passive"))
      (node (ref "R2") (pin "1") (pinfunction "1_1") (pintype "passive"))
    )
    (net (code "90") (name "Net-(D1-5)") (class "Default")
      (node (ref "D1") (pin "1") (pinfunction "5_1") (pintype "passive"))
      (node (ref "R1") (pin "1") (pinfunction "1_1") (pintype "passive"))
      (node (ref "UXBEE") (pin "3") (pinfunction "DIN/~{CONFIG}_3") (pintype "passive"))
    )
    (net (code "91") (name "Net-(D2-6)") (class "Default")
      (node (ref "C4") (pin "2") (pinfunction "2_2") (pintype "passive"))
      (node (ref "D2") (pin "2") (pinfunction "6_2") (pintype "passive"))
      (node (ref "L1") (pin "2") (pintype "passive"))
      (node (ref "U4") (pin "3") (pinfunction "SW_3") (pintype "power_in"))
    )
    (net (code "92") (name "Net-(D3-Pad1)") (class "Default")
      (node (ref "D3") (pin "1") (pinfunction "1_1") (pintype "passive"))
      (node (ref "R24") (pin "2") (pinfunction "2_2") (pintype "passive"))
    )
    (net (code "93") (name "Net-(D4-Pad1)") (class "Default")
      (node (ref "D4") (pin "1") (pinfunction "1_1") (pintype "passive"))
      (node (ref "R20") (pin "2") (pinfunction "2_2") (pintype "passive"))
    )
    (net (code "94") (name "Net-(D5-Pad1)") (class "Default")
      (node (ref "D5") (pin "1") (pinfunction "1_1") (pintype "passive"))
      (node (ref "R21") (pin "2") (pinfunction "2_2") (pintype "passive"))
    )
    (net (code "95") (name "Net-(D6-Pad2)") (class "Default")
      (node (ref "D6") (pin "2") (pinfunction "2_2") (pintype "passive"))
      (node (ref "R22") (pin "1") (pinfunction "1_1") (pintype "passive"))
    )
    (net (code "96") (name "Net-(D7-Pad2)") (class "Default")
      (node (ref "D7") (pin "2") (pinfunction "2_2") (pintype "passive"))
      (node (ref "R23") (pin "1") (pinfunction "1_1") (pintype "passive"))
    )
    (net (code "97") (name "Net-(H1-CCP)") (class "Default")
      (node (ref "C21") (pin "2") (pinfunction "2_2") (pintype "passive"))
      (node (ref "H1") (pin "36") (pinfunction "CCP_36") (pintype "passive"))
    )
    (net (code "98") (name "Net-(H2-CCP)") (class "Default")
      (node (ref "C25") (pin "2") (pinfunction "2_2") (pintype "passive"))
      (node (ref "H2") (pin "36") (pinfunction "CCP_36") (pintype "passive"))
    )
    (net (code "99") (name "Net-(H3-CP1)") (class "Default")
      (node (ref "H3") (pin "19") (pinfunction "CP1_19") (pintype "passive"))
      (node (ref "H3C1") (pin "1") (pinfunction "1_1") (pintype "passive"))
    )
    (net (code "100") (name "Net-(H3-CP2)") (class "Default")
      (node (ref "H3") (pin "1") (pinfunction "CP2_1") (pintype "passive"))
      (node (ref "H3C1") (pin "2") (pinfunction "2_2") (pintype "passive"))
    )
    (net (code "101") (name "Net-(H3-CP3)") (class "Default")
      (node (ref "H3") (pin "18") (pinfunction "CP3_18") (pintype "passive"))
      (node (ref "H3C2") (pin "2") (pinfunction "2_2") (pintype "passive"))
    )
    (net (code "102") (name "Net-(H3-CP4)") (class "Default")
      (node (ref "H3") (pin "20") (pinfunction "CP4_20") (pintype "passive"))
      (node (ref "H3C2") (pin "1") (pinfunction "1_1") (pintype "passive"))
    )
    (net (code "103") (name "Net-(H3-VCP)") (class "Default")
      (node (ref "H3") (pin "17") (pinfunction "VCP_17") (pintype "passive"))
      (node (ref "H3C3") (pin "2") (pinfunction "2_2") (pintype "passive"))
    )
    (net (code "104") (name "Net-(H4-CP1)") (class "Default")
      (node (ref "H4") (pin "19") (pinfunction "CP1_19") (pintype "passive"))
      (node (ref "H4C1") (pin "1") (pinfunction "1_1") (pintype "passive"))
    )
    (net (code "105") (name "Net-(H4-CP2)") (class "Default")
      (node (ref "H4") (pin "1") (pinfunction "CP2_1") (pintype "passive"))
      (node (ref "H4C1") (pin "2") (pinfunction "2_2") (pintype "passive"))
    )
    (net (code "106") (name "Net-(H4-CP3)") (class "Default")
      (node (ref "H4") (pin "18") (pinfunction "CP3_18") (pintype "passive"))
      (node (ref "H4C2") (pin "2") (pinfunction "2_2") (pintype "passive"))
    )
    (net (code "107") (name "Net-(H4-CP4)") (class "Default")
      (node (ref "H4") (pin "20") (pinfunction "CP4_20") (pintype "passive"))
      (node (ref "H4C2") (pin "1") (pinfunction "1_1") (pintype "passive"))
    )
    (net (code "108") (name "Net-(H4-VCP)") (class "Default")
      (node (ref "H4") (pin "17") (pinfunction "VCP_17") (pintype "passive"))
      (node (ref "H4C3") (pin "2") (pinfunction "2_2") (pintype "passive"))
    )
    (net (code "109") (name "Net-(U1-PA0_(AD0))") (class "Default")
      (node (ref "R22") (pin "2") (pinfunction "2_2") (pintype "passive"))
      (node (ref "U1") (pin "78") (pinfunction "PA0_(AD0)_78") (pintype "passive"))
    )
    (net (code "110") (name "Net-(U1-PA1_(AD1))") (class "Default")
      (node (ref "R23") (pin "2") (pinfunction "2_2") (pintype "passive"))
      (node (ref "U1") (pin "77") (pinfunction "PA1_(AD1)_77") (pintype "passive"))
    )
    (net (code "111") (name "Net-(U1-PL6)") (class "Default")
      (node (ref "R20") (pin "1") (pinfunction "1_1") (pintype "passive"))
      (node (ref "U1") (pin "41") (pinfunction "PL6_41") (pintype "passive"))
    )
    (net (code "112") (name "Net-(U1-PL7)") (class "Default")
      (node (ref "R21") (pin "1") (pinfunction "1_1") (pintype "passive"))
      (node (ref "U1") (pin "42") (pinfunction "PL7_42") (pintype "passive"))
    )
    (net (code "113") (name "Net-(U4-BOOST)") (class "Default")
      (node (ref "C4") (pin "1") (pinfunction "1_1") (pintype "passive"))
      (node (ref "U4") (pin "2") (pinfunction "BOOST_2") (pintype "passive"))
    )
    (net (code "114") (name "Net-(U4-FB)") (class "Default")
      (node (ref "R3") (pin "2") (pinfunction "2_2") (pintype "passive"))
      (node (ref "R4") (pin "1") (pinfunction "1_1") (pintype "passive"))
      (node (ref "U4") (pin "8") (pinfunction "FB_8") (pintype "input"))
    )
    (net (code "115") (name "Net-(U4-RT)") (class "Default")
      (node (ref "R5") (pin "1") (pinfunction "1_1") (pintype "passive"))
      (node (ref "U4") (pin "10") (pinfunction "RT_10") (pintype "passive"))
    )
    (net (code "116") (name "Net-(U4-VC)") (class "Default")
      (node (ref "R2") (pin "2") (pinfunction "2_2") (pintype "passive"))
      (node (ref "U4") (pin "9") (pinfunction "VC_9") (pintype "passive"))
    )
    (net (code "117") (name "Net-(U6-FCKI)") (class "Default")
      (node (ref "C35") (pin "1") (pinfunction "1_1") (pintype "passive"))
      (node (ref "R61") (pin "1") (pinfunction "1_1") (pintype "passive"))
      (node (ref "U6") (pin "2") (pinfunction "FCKI_2") (pintype "passive"))
      (node (ref "X2") (pin "4") (pinfunction "OSC1_4") (pintype "passive"))
    )
    (net (code "118") (name "Net-(U6-FCKO)") (class "Default")
      (node (ref "C36") (pin "1") (pinfunction "1_1") (pintype "passive"))
      (node (ref "R61") (pin "2") (pinfunction "2_2") (pintype "passive"))
      (node (ref "U6") (pin "1") (pinfunction "FCKO_1") (pintype "passive"))
      (node (ref "X2") (pin "2") (pinfunction "OSC2_2") (pintype "passive"))
    )
    (net (code "119") (name "Net-(U8-FCKI)") (class "Default")
      (node (ref "C37") (pin "1") (pinfunction "1_1") (pintype "passive"))
      (node (ref "R62") (pin "1") (pinfunction "1_1") (pintype "passive"))
      (node (ref "U8") (pin "2") (pinfunction "FCKI_2") (pintype "passive"))
      (node (ref "X3") (pin "4") (pinfunction "OSC1_4") (pintype "passive"))
    )
    (net (code "120") (name "Net-(U8-FCKO)") (class "Default")
      (node (ref "C38") (pin "1") (pinfunction "1_1") (pintype "passive"))
      (node (ref "R62") (pin "2") (pinfunction "2_2") (pintype "passive"))
      (node (ref "U8") (pin "1") (pinfunction "FCKO_1") (pintype "passive"))
      (node (ref "X3") (pin "2") (pinfunction "OSC2_2") (pintype "passive"))
    )
    (net (code "121") (name "Net-(U10-FCKI)") (class "Default")
      (node (ref "C39") (pin "1") (pinfunction "1_1") (pintype "passive"))
      (node (ref "R63") (pin "1") (pinfunction "1_1") (pintype "passive"))
      (node (ref "U10") (pin "2") (pinfunction "FCKI_2") (pintype "passive"))
      (node (ref "X4") (pin "4") (pinfunction "OSC1_4") (pintype "passive"))
    )
    (net (code "122") (name "Net-(U10-FCKO)") (class "Default")
      (node (ref "C40") (pin "1") (pinfunction "1_1") (pintype "passive"))
      (node (ref "R63") (pin "2") (pinfunction "2_2") (pintype "passive"))
      (node (ref "U10") (pin "1") (pinfunction "FCKO_1") (pintype "passive"))
      (node (ref "X4") (pin "2") (pinfunction "OSC2_2") (pintype "passive"))
    )
    (net (code "123") (name "Net-(U12-FCKI)") (class "Default")
      (node (ref "C41") (pin "1") (pinfunction "1_1") (pintype "passive"))
      (node (ref "R64") (pin "1") (pinfunction "1_1") (pintype "passive"))
      (node (ref "U12") (pin "2") (pinfunction "FCKI_2") (pintype "passive"))
      (node (ref "X5") (pin "4") (pinfunction "OSC1_4") (pintype "passive"))
    )
    (net (code "124") (name "Net-(U12-FCKO)") (class "Default")
      (node (ref "C42") (pin "1") (pinfunction "1_1") (pintype "passive"))
      (node (ref "R64") (pin "2") (pinfunction "2_2") (pintype "passive"))
      (node (ref "U12") (pin "1") (pinfunction "FCKO_1") (pintype "passive"))
      (node (ref "X5") (pin "2") (pinfunction "OSC2_2") (pintype "passive"))
    )
    (net (code "125") (name "Net-(U14-FCKI)") (class "Default")
      (node (ref "C56") (pin "1") (pinfunction "1_1") (pintype "passive"))
      (node (ref "R65") (pin "1") (pinfunction "1_1") (pintype "passive"))
      (node (ref "U14") (pin "2") (pinfunction "FCKI_2") (pintype "passive"))
      (node (ref "X6") (pin "4") (pinfunction "OSC1_4") (pintype "passive"))
    )
    (net (code "126") (name "Net-(U14-FCKO)") (class "Default")
      (node (ref "C57") (pin "1") (pinfunction "1_1") (pintype "passive"))
      (node (ref "R65") (pin "2") (pinfunction "2_2") (pintype "passive"))
      (node (ref "U14") (pin "1") (pinfunction "FCKO_1") (pintype "passive"))
      (node (ref "X6") (pin "2") (pinfunction "OSC2_2") (pintype "passive"))
    )
    (net (code "127") (name "Net-(U16-FCKI)") (class "Default")
      (node (ref "C58") (pin "1") (pinfunction "1_1") (pintype "passive"))
      (node (ref "R66") (pin "1") (pinfunction "1_1") (pintype "passive"))
      (node (ref "U16") (pin "2") (pinfunction "FCKI_2") (pintype "passive"))
      (node (ref "X7") (pin "4") (pinfunction "OSC1_4") (pintype "passive"))
    )
    (net (code "128") (name "Net-(U16-FCKO)") (class "Default")
      (node (ref "C59") (pin "1") (pinfunction "1_1") (pintype "passive"))
      (node (ref "R66") (pin "2") (pinfunction "2_2") (pintype "passive"))
      (node (ref "U16") (pin "1") (pinfunction "FCKO_1") (pintype "passive"))
      (node (ref "X7") (pin "2") (pinfunction "OSC2_2") (pintype "passive"))
    )
    (net (code "129") (name "Net-(UXBEE-AD3{slash}DIO3)") (class "Default")
      (node (ref "R26") (pin "1") (pinfunction "1_1") (pintype "passive"))
      (node (ref "UXBEE") (pin "17") (pinfunction "AD3/DIO3_17") (pintype "passive"))
    )
    (net (code "130") (name "unconnected-(H1-NC-Pad1)") (class "Default")
      (node (ref "H1") (pin "1") (pinfunction "NC_1") (pintype "passive"))
    )
    (net (code "131") (name "unconnected-(H1-NC-Pad7)") (class "Default")
      (node (ref "H1") (pin "7") (pinfunction "NC_7") (pintype "passive"))
    )
    (net (code "132") (name "unconnected-(H1-NC-Pad10)") (class "Default")
      (node (ref "H1") (pin "10") (pinfunction "NC_10") (pintype "passive"))
    )
    (net (code "133") (name "unconnected-(H1-NC-Pad16)") (class "Default")
      (node (ref "H1") (pin "16") (pinfunction "NC_16") (pintype "passive"))
    )
    (net (code "134") (name "unconnected-(H1-NC-Pad19)") (class "Default")
      (node (ref "H1") (pin "19") (pinfunction "NC_19") (pintype "passive"))
    )
    (net (code "135") (name "unconnected-(H1-NC-Pad28)") (class "Default")
      (node (ref "H1") (pin "28") (pinfunction "NC_28") (pintype "passive"))
    )
    (net (code "136") (name "unconnected-(H1-NC-Pad31)") (class "Default")
      (node (ref "H1") (pin "31") (pinfunction "NC_31") (pintype "passive"))
    )
    (net (code "137") (name "unconnected-(H2-NC-Pad1)") (class "Default")
      (node (ref "H2") (pin "1") (pinfunction "NC_1") (pintype "passive"))
    )
    (net (code "138") (name "unconnected-(H2-NC-Pad7)") (class "Default")
      (node (ref "H2") (pin "7") (pinfunction "NC_7") (pintype "passive"))
    )
    (net (code "139") (name "unconnected-(H2-NC-Pad10)") (class "Default")
      (node (ref "H2") (pin "10") (pinfunction "NC_10") (pintype "passive"))
    )
    (net (code "140") (name "unconnected-(H2-NC-Pad16)") (class "Default")
      (node (ref "H2") (pin "16") (pinfunction "NC_16") (pintype "passive"))
    )
    (net (code "141") (name "unconnected-(H2-NC-Pad19)") (class "Default")
      (node (ref "H2") (pin "19") (pinfunction "NC_19") (pintype "passive"))
    )
    (net (code "142") (name "unconnected-(H2-NC-Pad28)") (class "Default")
      (node (ref "H2") (pin "28") (pinfunction "NC_28") (pintype "passive"))
    )
    (net (code "143") (name "unconnected-(H2-NC-Pad31)") (class "Default")
      (node (ref "H2") (pin "31") (pinfunction "NC_31") (pintype "passive"))
    )
    (net (code "144") (name "unconnected-(MS1-NC-Pad4)") (class "Default")
      (node (ref "MS1") (pin "4") (pinfunction "NC_4") (pintype "passive"))
    )
    (net (code "145") (name "unconnected-(MS1-SDO-Pad8)") (class "Default")
      (node (ref "MS1") (pin "8") (pinfunction "SDO_8") (pintype "passive"))
    )
    (net (code "146") (name "unconnected-(S1-GND-Pad1)") (class "Default")
      (node (ref "S1") (pin "1") (pinfunction "GND_1") (pintype "passive"))
    )
    (net (code "147") (name "unconnected-(S1-GND-Pad2)") (class "Default")
      (node (ref "S1") (pin "2") (pinfunction "GND_2") (pintype "passive"))
    )
    (net (code "148") (name "unconnected-(S2-GND-Pad1)") (class "Default")
      (node (ref "S2") (pin "1") (pinfunction "GND_1") (pintype "passive"))
    )
    (net (code "149") (name "unconnected-(S2-GND-Pad2)") (class "Default")
      (node (ref "S2") (pin "2") (pinfunction "GND_2") (pintype "passive"))
    )
    (net (code "150") (name "unconnected-(S3-GND-Pad1)") (class "Default")
      (node (ref "S3") (pin "1") (pinfunction "GND_1") (pintype "passive"))
    )
    (net (code "151") (name "unconnected-(S3-GND-Pad2)") (class "Default")
      (node (ref "S3") (pin "2") (pinfunction "GND_2") (pintype "passive"))
    )
    (net (code "152") (name "unconnected-(U1-PA2_(AD2)-Pad76)") (class "Default")
      (node (ref "U1") (pin "76") (pinfunction "PA2_(AD2)_76") (pintype "passive"))
    )
    (net (code "153") (name "unconnected-(U1-PA3_(AD3)-Pad75)") (class "Default")
      (node (ref "U1") (pin "75") (pinfunction "PA3_(AD3)_75") (pintype "passive"))
    )
    (net (code "154") (name "unconnected-(U1-PA4_(AD4)-Pad74)") (class "Default")
      (node (ref "U1") (pin "74") (pinfunction "PA4_(AD4)_74") (pintype "passive"))
    )
    (net (code "155") (name "unconnected-(U1-PA5_(AD5)-Pad73)") (class "Default")
      (node (ref "U1") (pin "73") (pinfunction "PA5_(AD5)_73") (pintype "passive"))
    )
    (net (code "156") (name "unconnected-(U1-PA6_(AD6)-Pad72)") (class "Default")
      (node (ref "U1") (pin "72") (pinfunction "PA6_(AD6)_72") (pintype "passive"))
    )
    (net (code "157") (name "unconnected-(U1-PA7_(AD7)-Pad71)") (class "Default")
      (node (ref "U1") (pin "71") (pinfunction "PA7_(AD7)_71") (pintype "passive"))
    )
    (net (code "158") (name "unconnected-(U1-PC7_(A15)-Pad60)") (class "Default")
      (node (ref "U1") (pin "60") (pinfunction "PC7_(A15)_60") (pintype "passive"))
    )
    (net (code "159") (name "unconnected-(U1-PD4_(ICP1)-Pad47)") (class "Default")
      (node (ref "U1") (pin "47") (pinfunction "PD4_(ICP1)_47") (pintype "passive"))
    )
    (net (code "160") (name "unconnected-(U1-PD5_(XCK1)-Pad48)") (class "Default")
      (node (ref "U1") (pin "48") (pinfunction "PD5_(XCK1)_48") (pintype "passive"))
    )
    (net (code "161") (name "unconnected-(U1-PD6_(T1)-Pad49)") (class "Default")
      (node (ref "U1") (pin "49") (pinfunction "PD6_(T1)_49") (pintype "passive"))
    )
    (net (code "162") (name "unconnected-(U1-PD7_(T0)-Pad50)") (class "Default")
      (node (ref "U1") (pin "50") (pinfunction "PD7_(T0)_50") (pintype "passive"))
    )
    (net (code "163") (name "unconnected-(U1-PF0_(ADC0)-Pad97)") (class "Default")
      (node (ref "U1") (pin "97") (pinfunction "PF0_(ADC0)_97") (pintype "passive"))
    )
    (net (code "164") (name "unconnected-(U1-PF7_(ADC7{slash}PCINT15)-Pad90)") (class "Default")
      (node (ref "U1") (pin "90") (pinfunction "PF7_(ADC7/PCINT15)_90") (pintype "passive"))
    )
    (net (code "165") (name "unconnected-(U1-PG2_(ALE)-Pad70)") (class "Default")
      (node (ref "U1") (pin "70") (pinfunction "PG2_(ALE)_70") (pintype "passive"))
    )
    (net (code "166") (name "unconnected-(U1-PG4(TOSC1)-Pad29)") (class "Default")
      (node (ref "U1") (pin "29") (pinfunction "PG4(TOSC1)_29") (pintype "passive"))
    )
    (net (code "167") (name "unconnected-(U1-PJ2_(XCK3{slash}PCINT11)-Pad65)") (class "Default")
      (node (ref "U1") (pin "65") (pinfunction "PJ2_(XCK3/PCINT11)_65") (pintype "passive"))
    )
    (net (code "168") (name "unconnected-(U1-PJ3_(PCINT12)-Pad66)") (class "Default")
      (node (ref "U1") (pin "66") (pinfunction "PJ3_(PCINT12)_66") (pintype "passive"))
    )
    (net (code "169") (name "unconnected-(U1-PJ4_(PCINT13)-Pad67)") (class "Default")
      (node (ref "U1") (pin "67") (pinfunction "PJ4_(PCINT13)_67") (pintype "passive"))
    )
    (net (code "170") (name "unconnected-(U1-PJ5_(PCINT14)-Pad68)") (class "Default")
      (node (ref "U1") (pin "68") (pinfunction "PJ5_(PCINT14)_68") (pintype "passive"))
    )
    (net (code "171") (name "unconnected-(U1-PJ6_(PCINT15)-Pad69)") (class "Default")
      (node (ref "U1") (pin "69") (pinfunction "PJ6_(PCINT15)_69") (pintype "passive"))
    )
    (net (code "172") (name "unconnected-(U1-PJ7-Pad79)") (class "Default")
      (node (ref "U1") (pin "79") (pinfunction "PJ7_79") (pintype "passive"))
    )
    (net (code "173") (name "unconnected-(U1-PK0_(ADC8{slash}PCINT16)-Pad89)") (class "Default")
      (node (ref "U1") (pin "89") (pinfunction "PK0_(ADC8/PCINT16)_89") (pintype "passive"))
    )
    (net (code "174") (name "unconnected-(U1-XTAL1-Pad33)") (class "Default")
      (node (ref "U1") (pin "33") (pinfunction "XTAL1_33") (pintype "passive"))
    )
    (net (code "175") (name "unconnected-(U1-XTAL2-Pad34)") (class "Default")
      (node (ref "U1") (pin "34") (pinfunction "XTAL2_34") (pintype "passive"))
    )
    (net (code "176") (name "unconnected-(U4-PG-Pad7)") (class "Default")
      (node (ref "U4") (pin "7") (pinfunction "PG_7") (pintype "open_collector"))
    )
    (net (code "177") (name "unconnected-(UXBEE-AD0{slash}DIO0-Pad20)") (class "Default")
      (node (ref "UXBEE") (pin "20") (pinfunction "AD0/DIO0_20") (pintype "passive"))
    )
    (net (code "178") (name "unconnected-(UXBEE-AD1{slash}DIO1-Pad19)") (class "Default")
      (node (ref "UXBEE") (pin "19") (pinfunction "AD1/DIO1_19") (pintype "passive"))
    )
    (net (code "179") (name "unconnected-(UXBEE-AD2{slash}DIO2-Pad18)") (class "Default")
      (node (ref "UXBEE") (pin "18") (pinfunction "AD2/DIO2_18") (pintype "passive"))
    )
    (net (code "180") (name "unconnected-(UXBEE-AD4{slash}DIO4-Pad11)") (class "Default")
      (node (ref "UXBEE") (pin "11") (pinfunction "AD4/DIO4_11") (pintype "passive"))
    )
    (net (code "181") (name "unconnected-(UXBEE-AD5{slash}DIO5{slash}AI-Pad15)") (class "Default")
      (node (ref "UXBEE") (pin "15") (pinfunction "AD5/DIO5/AI_15") (pintype "passive"))
    )
    (net (code "182") (name "unconnected-(UXBEE-AD6{slash}DIO6{slash}~{RTS}-Pad16)") (class "Default")
      (node (ref "UXBEE") (pin "16") (pinfunction "AD6/DIO6/~{RTS}_16") (pintype "passive"))
    )
    (net (code "183") (name "unconnected-(UXBEE-DIO7{slash}~{CTS}-Pad12)") (class "Default")
      (node (ref "UXBEE") (pin "12") (pinfunction "DIO7/~{CTS}_12") (pintype "passive"))
    )
    (net (code "184") (name "unconnected-(UXBEE-DO8-Pad4)") (class "Default")
      (node (ref "UXBEE") (pin "4") (pinfunction "DO8_4") (pintype "passive"))
    )
    (net (code "185") (name "unconnected-(UXBEE-NC-Pad8)") (class "Default")
      (node (ref "UXBEE") (pin "8") (pinfunction "NC_8") (pintype "passive"))
    )
    (net (code "186") (name "unconnected-(UXBEE-ON{slash}~{SLEEP}-Pad13)") (class "Default")
      (node (ref "UXBEE") (pin "13") (pinfunction "ON/~{SLEEP}_13") (pintype "passive"))
    )
    (net (code "187") (name "unconnected-(UXBEE-PWM0{slash}RSSI-Pad6)") (class "Default")
      (node (ref "UXBEE") (pin "6") (pinfunction "PWM0/RSSI_6") (pintype "passive"))
    )
    (net (code "188") (name "unconnected-(UXBEE-PWM1-Pad7)") (class "Default")
      (node (ref "UXBEE") (pin "7") (pinfunction "PWM1_7") (pintype "passive"))
    )
    (net (code "189") (name "unconnected-(UXBEE-SLEEP_RQ{slash}DI8{slash}~{DTR}-Pad9)") (class "Default")
      (node (ref "UXBEE") (pin "9") (pinfunction "SLEEP_RQ/DI8/~{DTR}_9") (pintype "passive"))
    )
    (net (code "190") (name "unconnected-(UXBEE-VREF-Pad14)") (class "Default")
      (node (ref "UXBEE") (pin "14") (pinfunction "VREF_14") (pintype "passive"))
    )
    (net (code "191") (name "unconnected-(UXBEE-~{RESET}-Pad5)") (class "Default")
      (node (ref "UXBEE") (pin "5") (pinfunction "~{RESET}_5") (pintype "passive"))
    )
  )
)
